# PKG900000001527.net
KiCad netlist of a schematic drawn in EAGLE
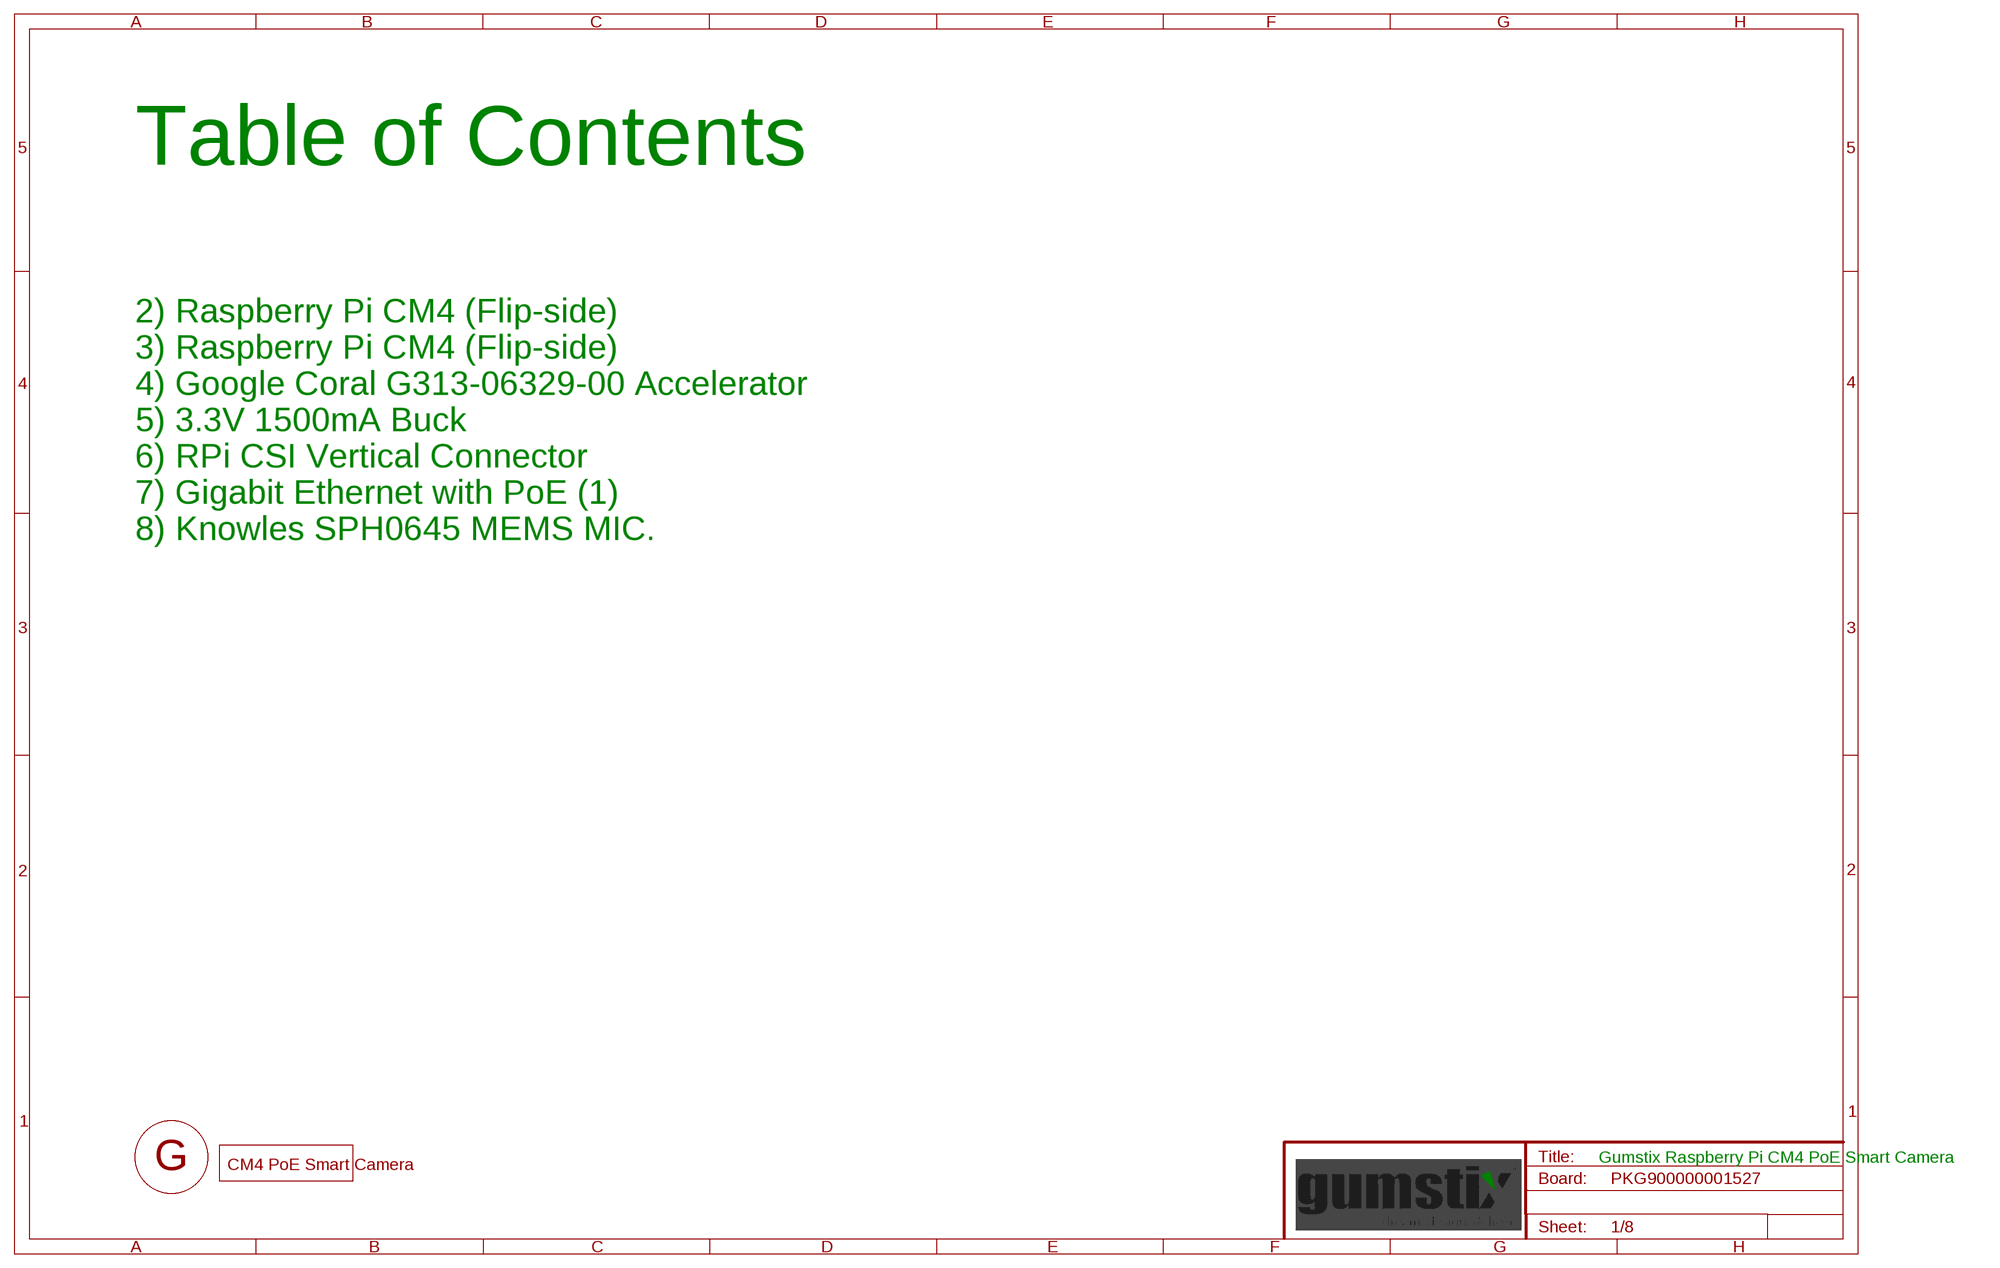
[diagram p0: schematic, sheet 1]
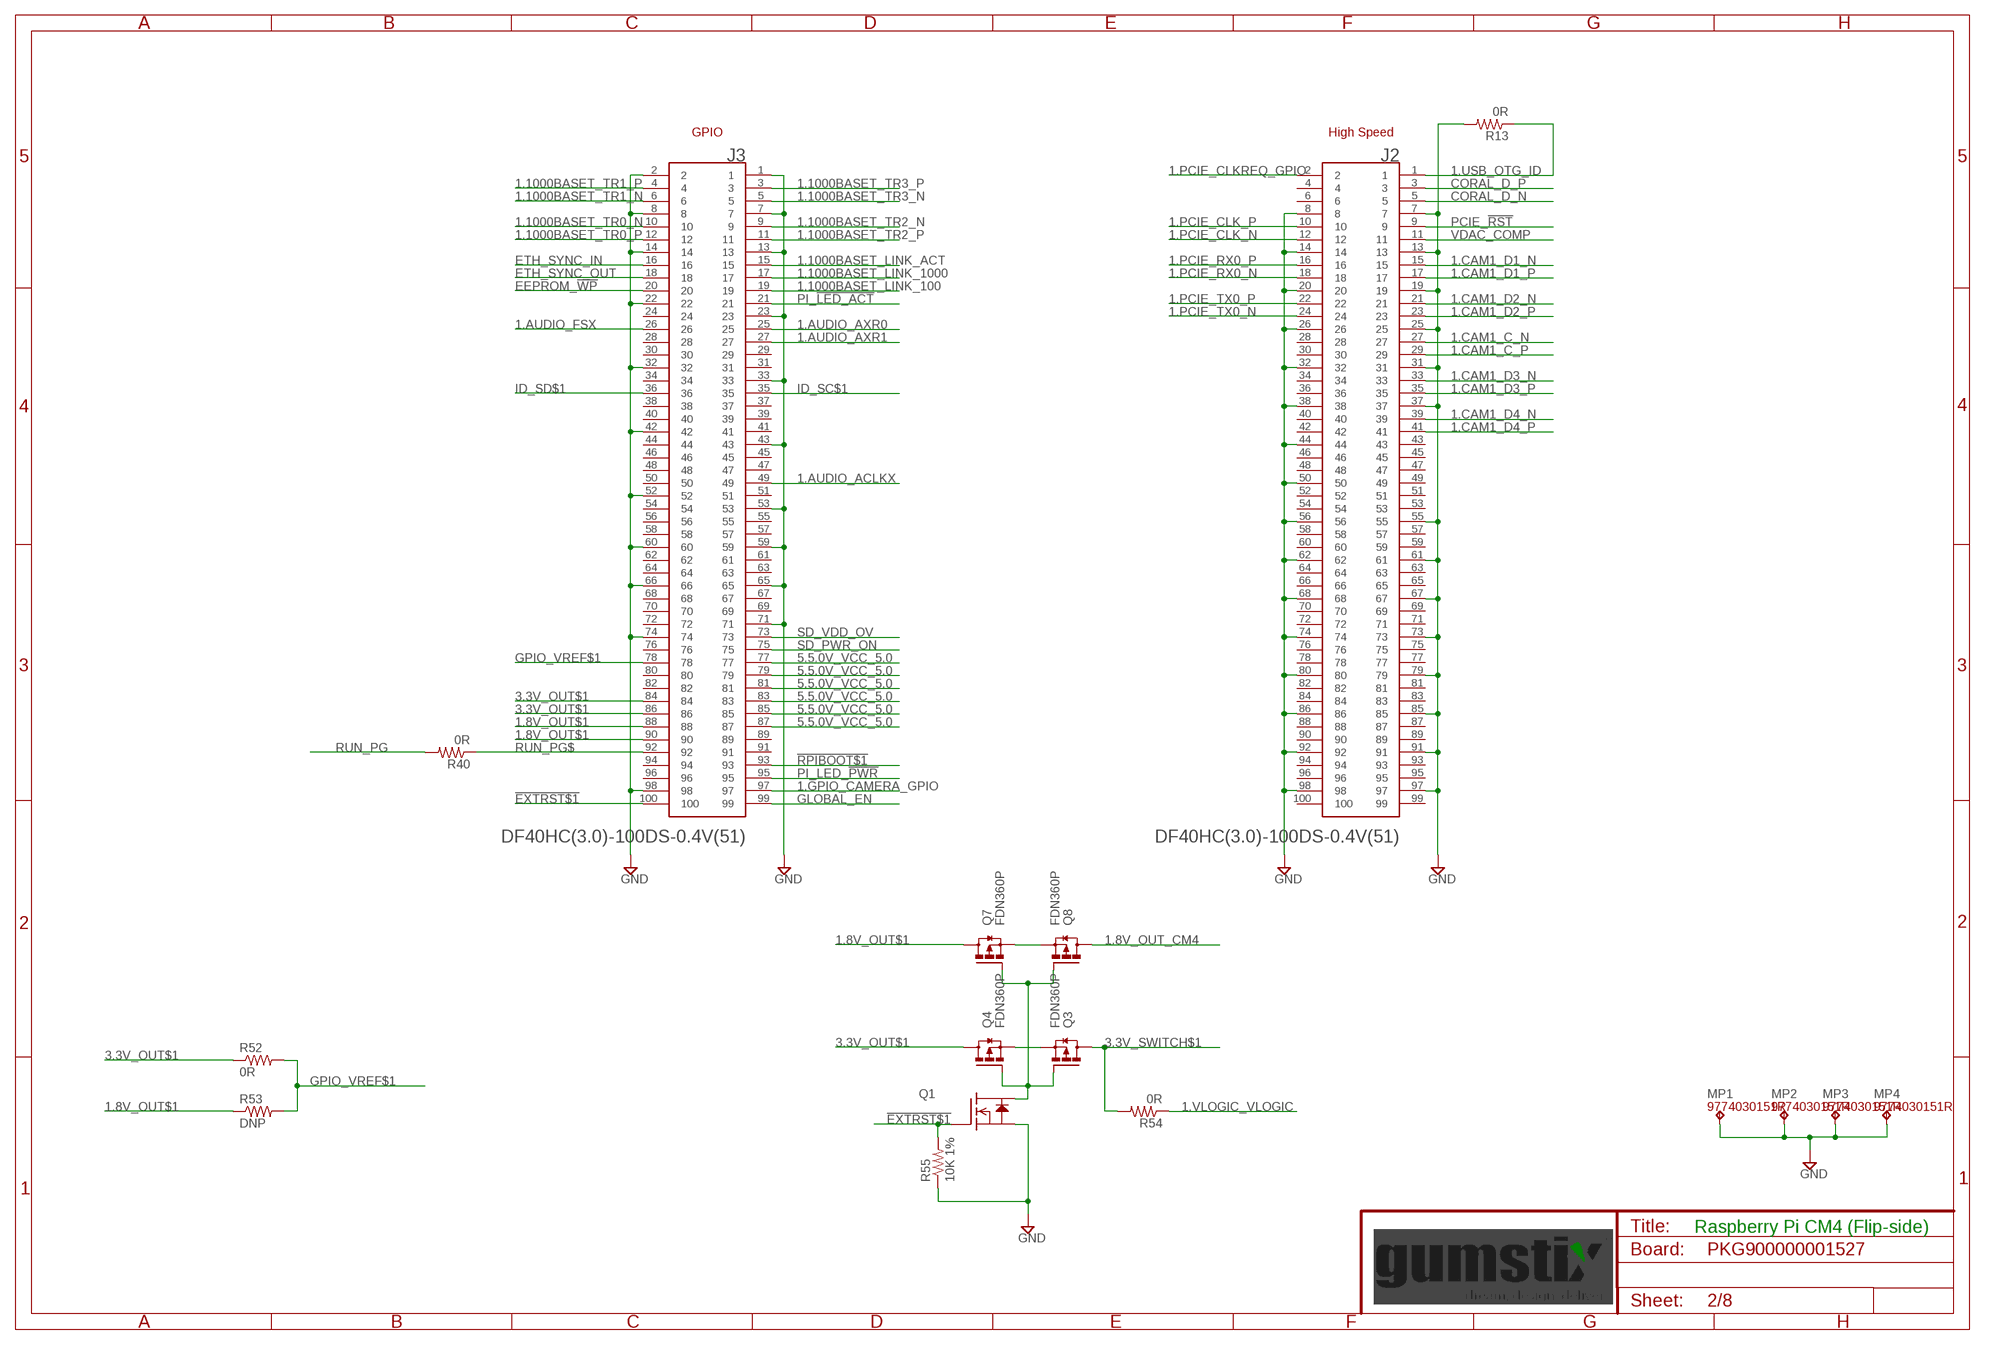
[diagram p1: schematic, sheet 2]
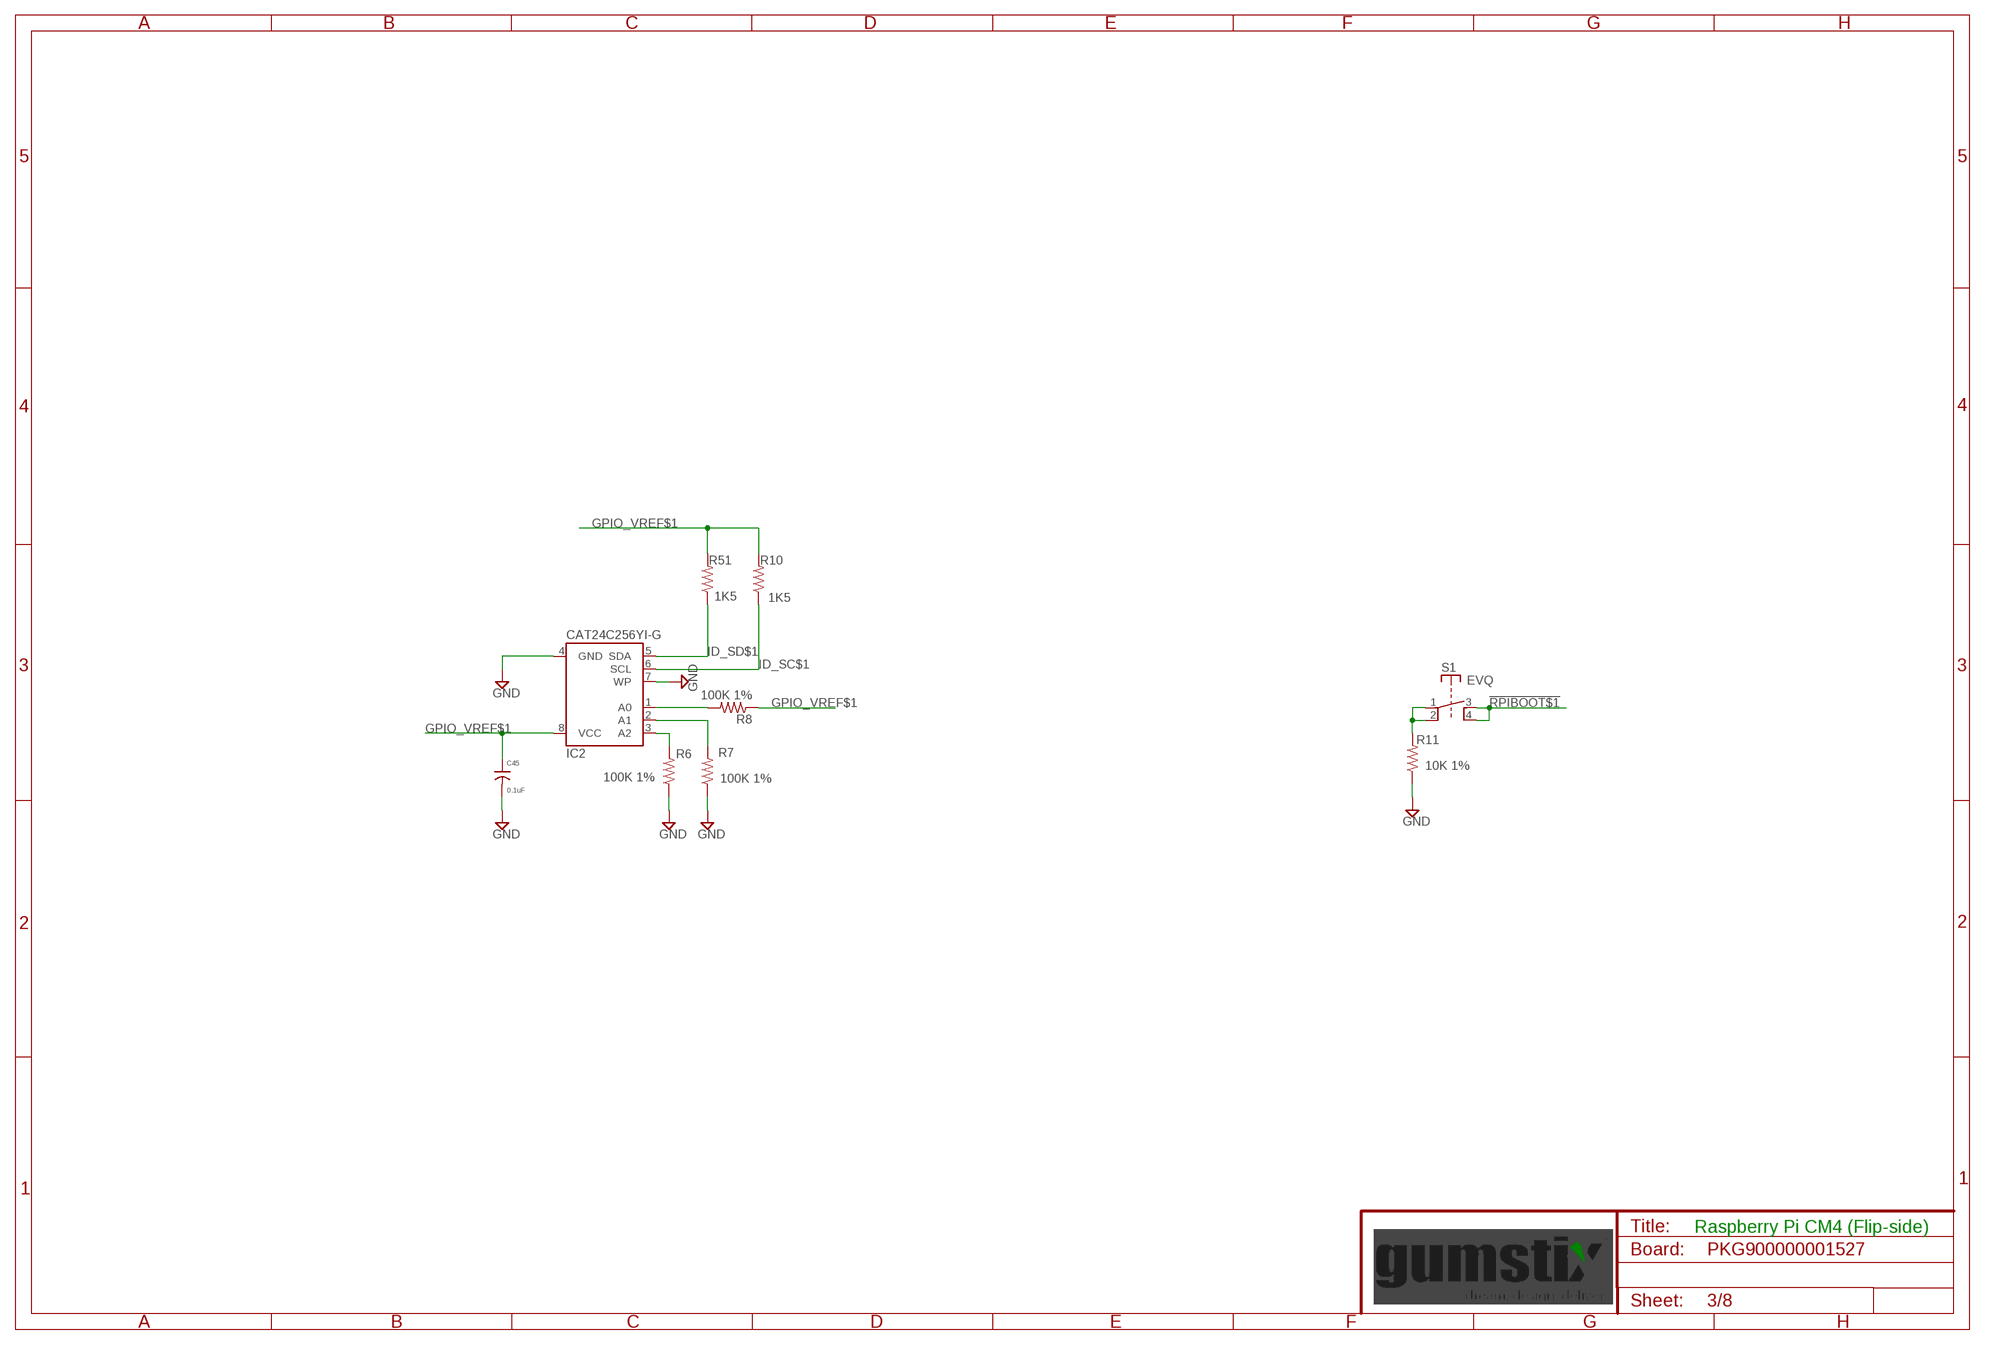
[diagram p2: schematic, sheet 3]
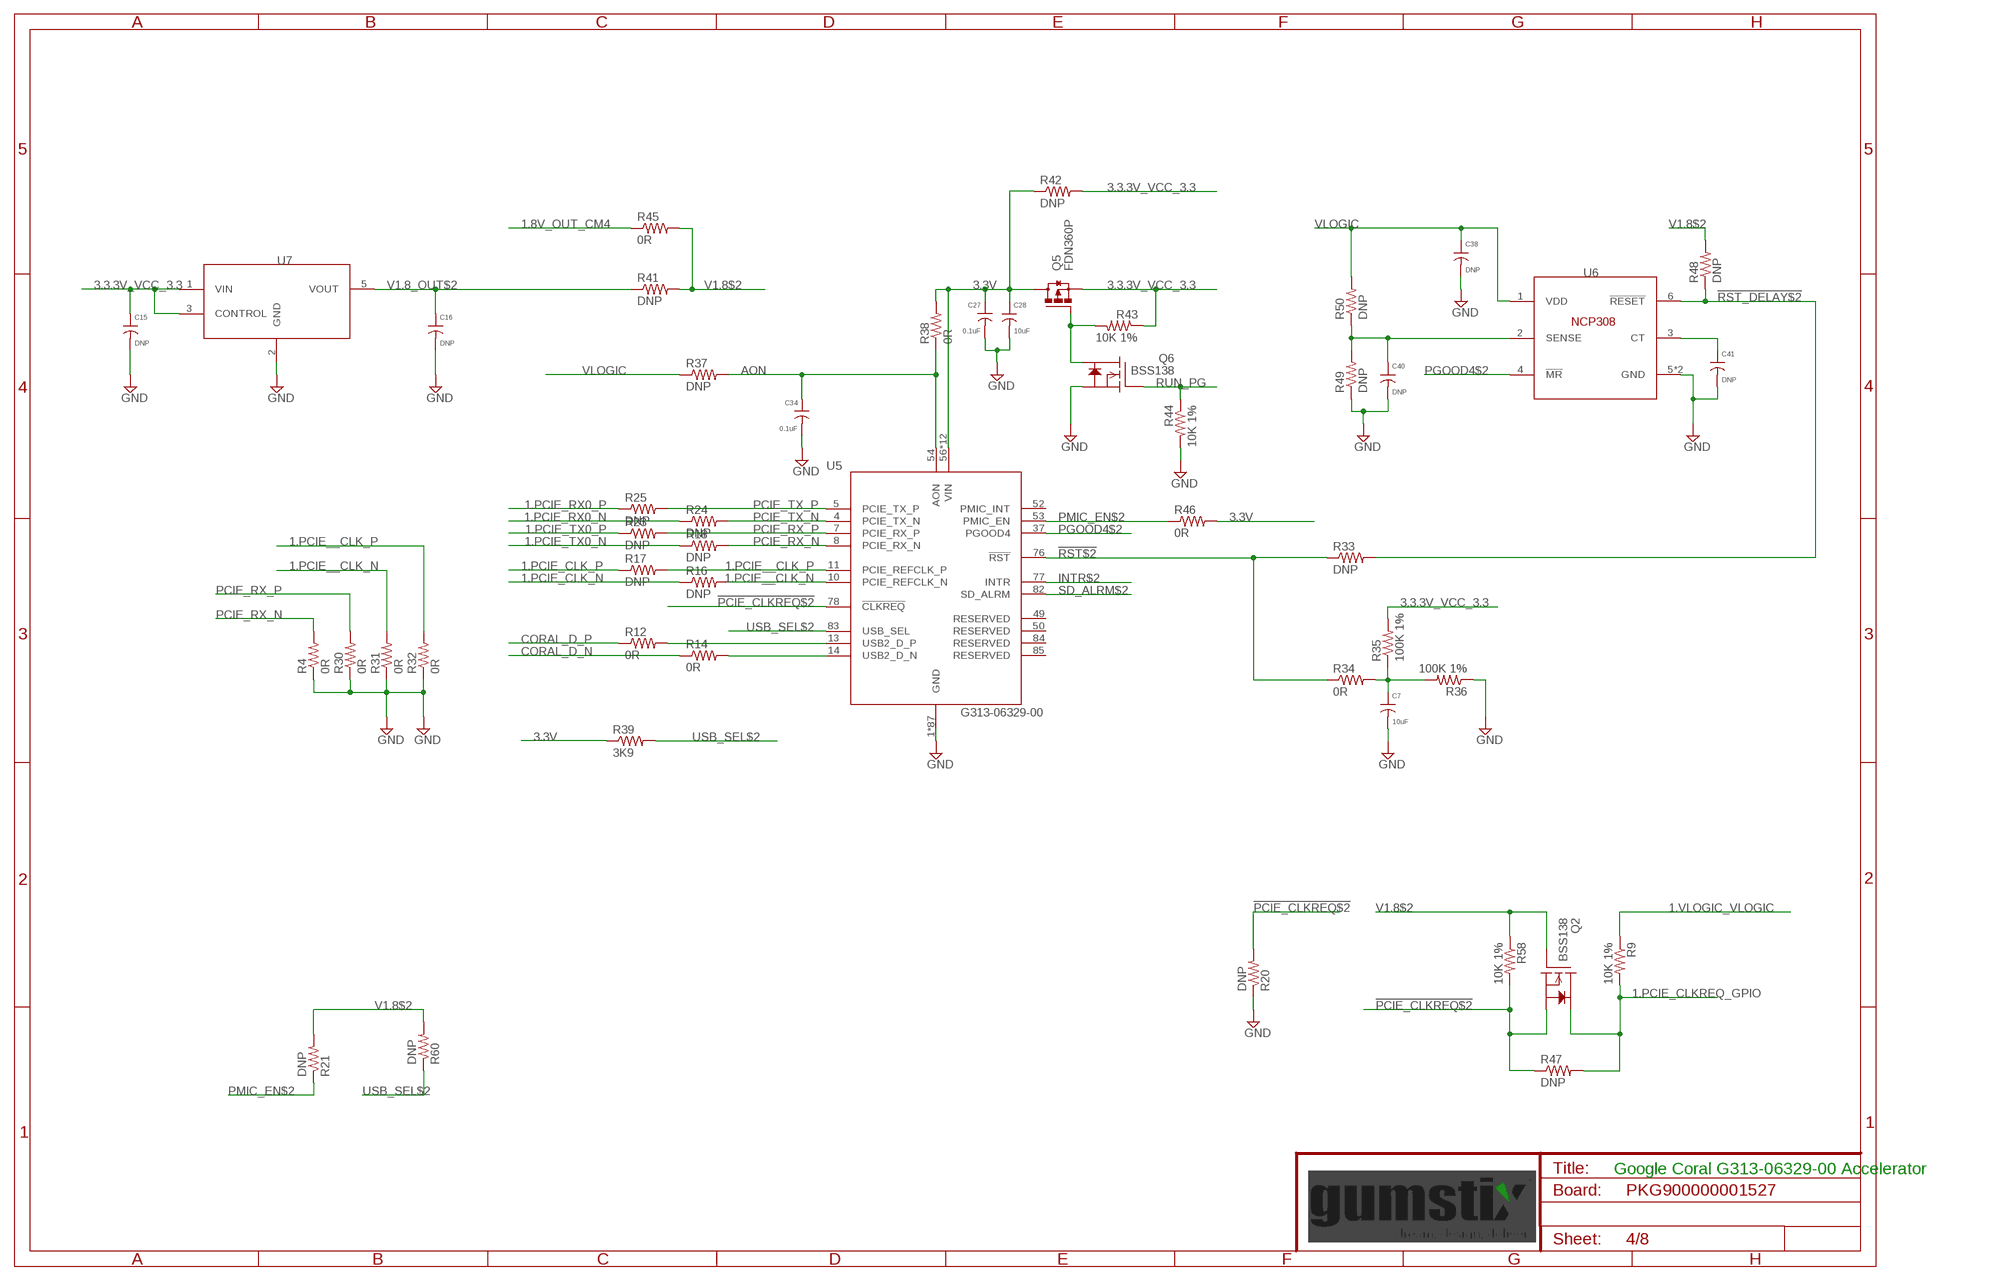
[diagram p3: schematic, sheet 4]
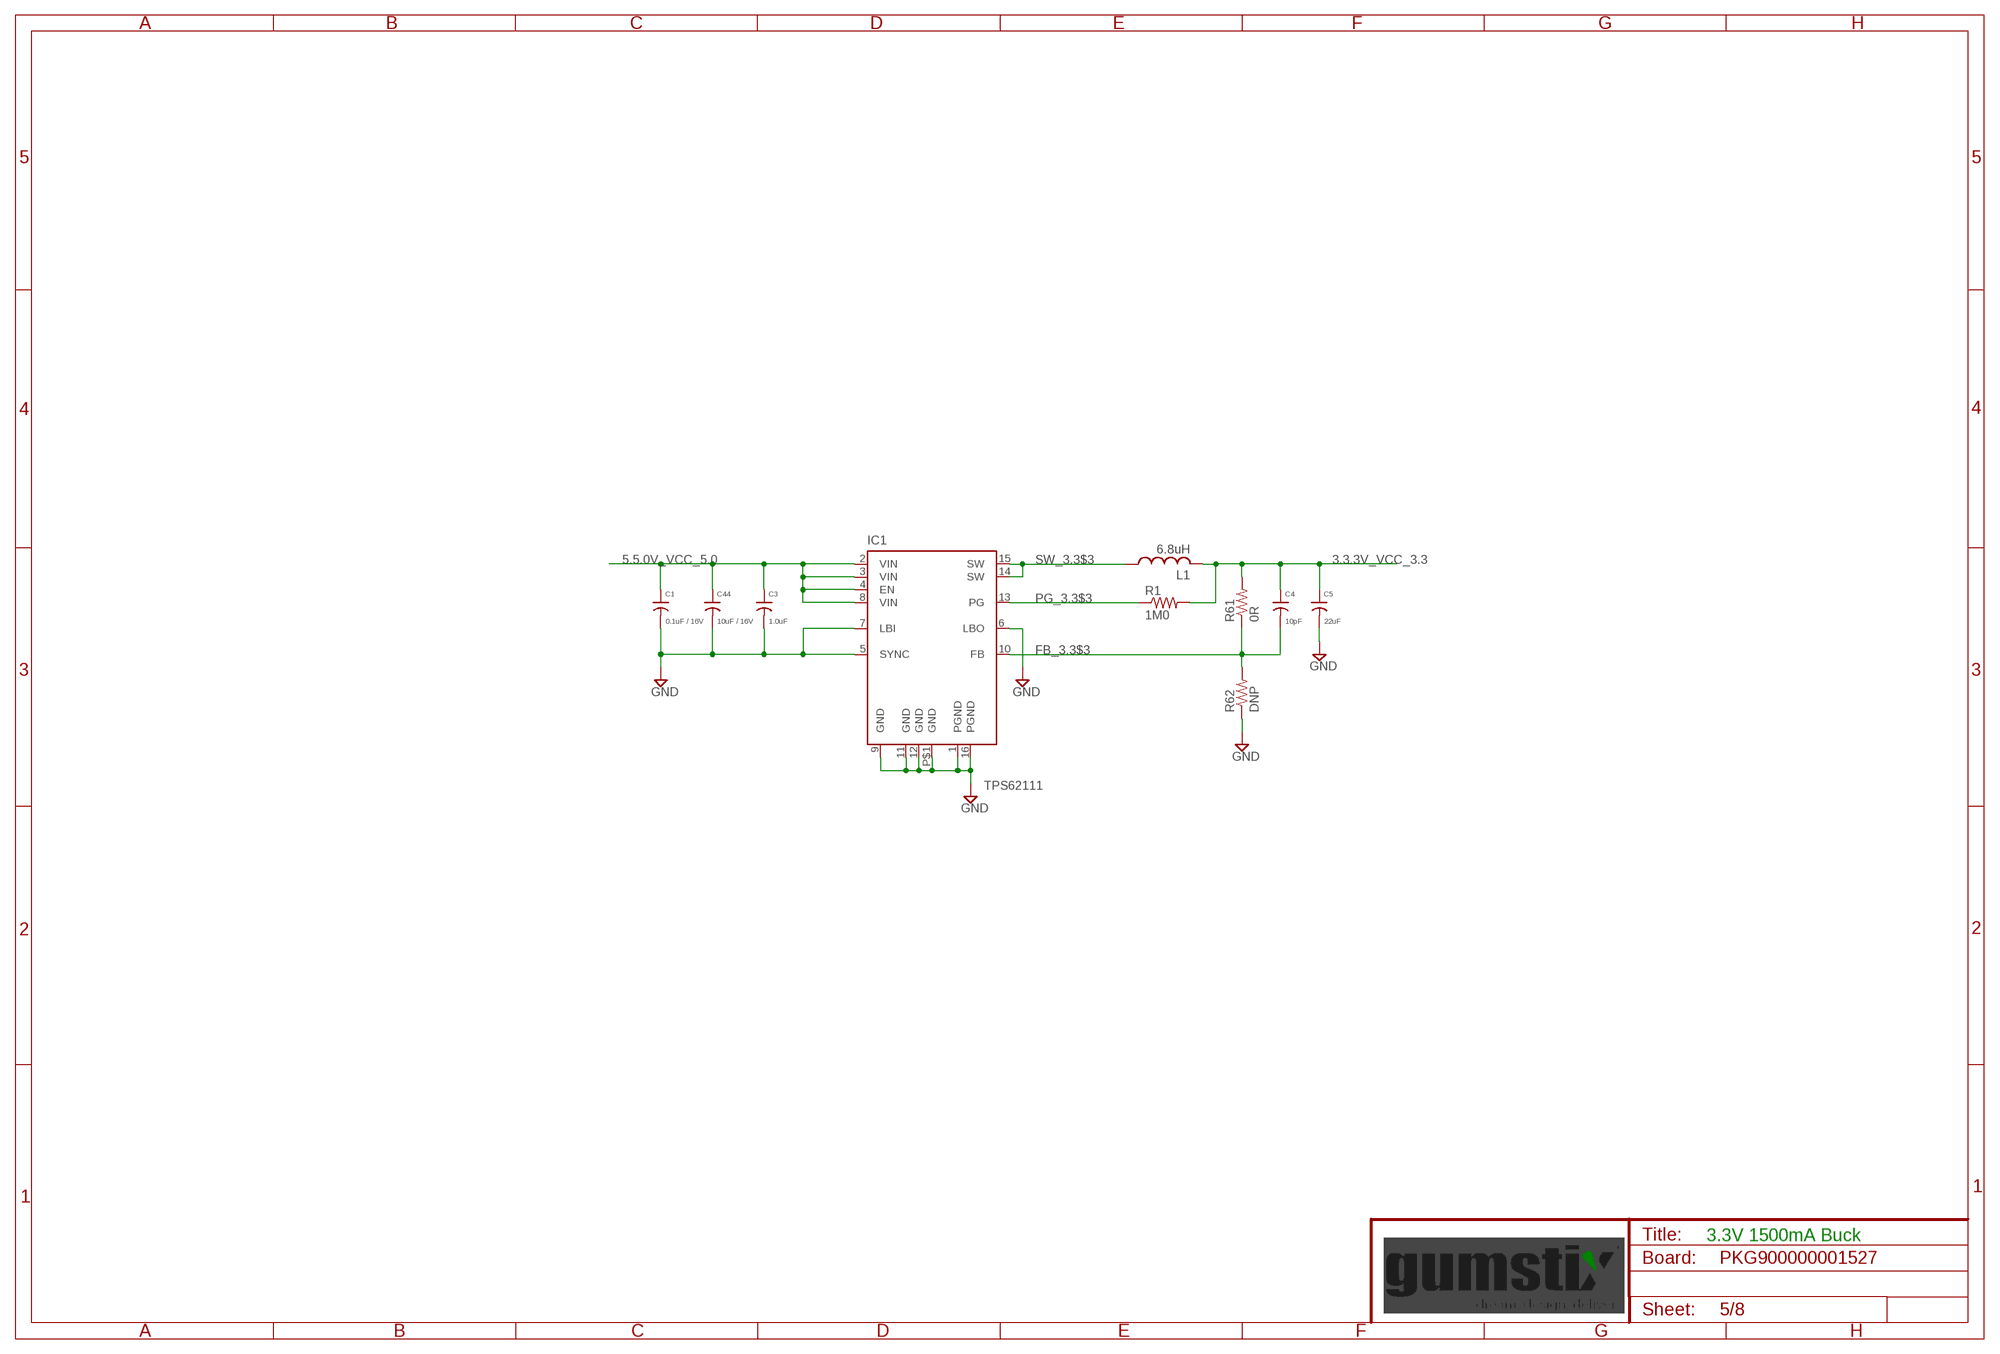
[diagram p4: schematic, sheet 5]
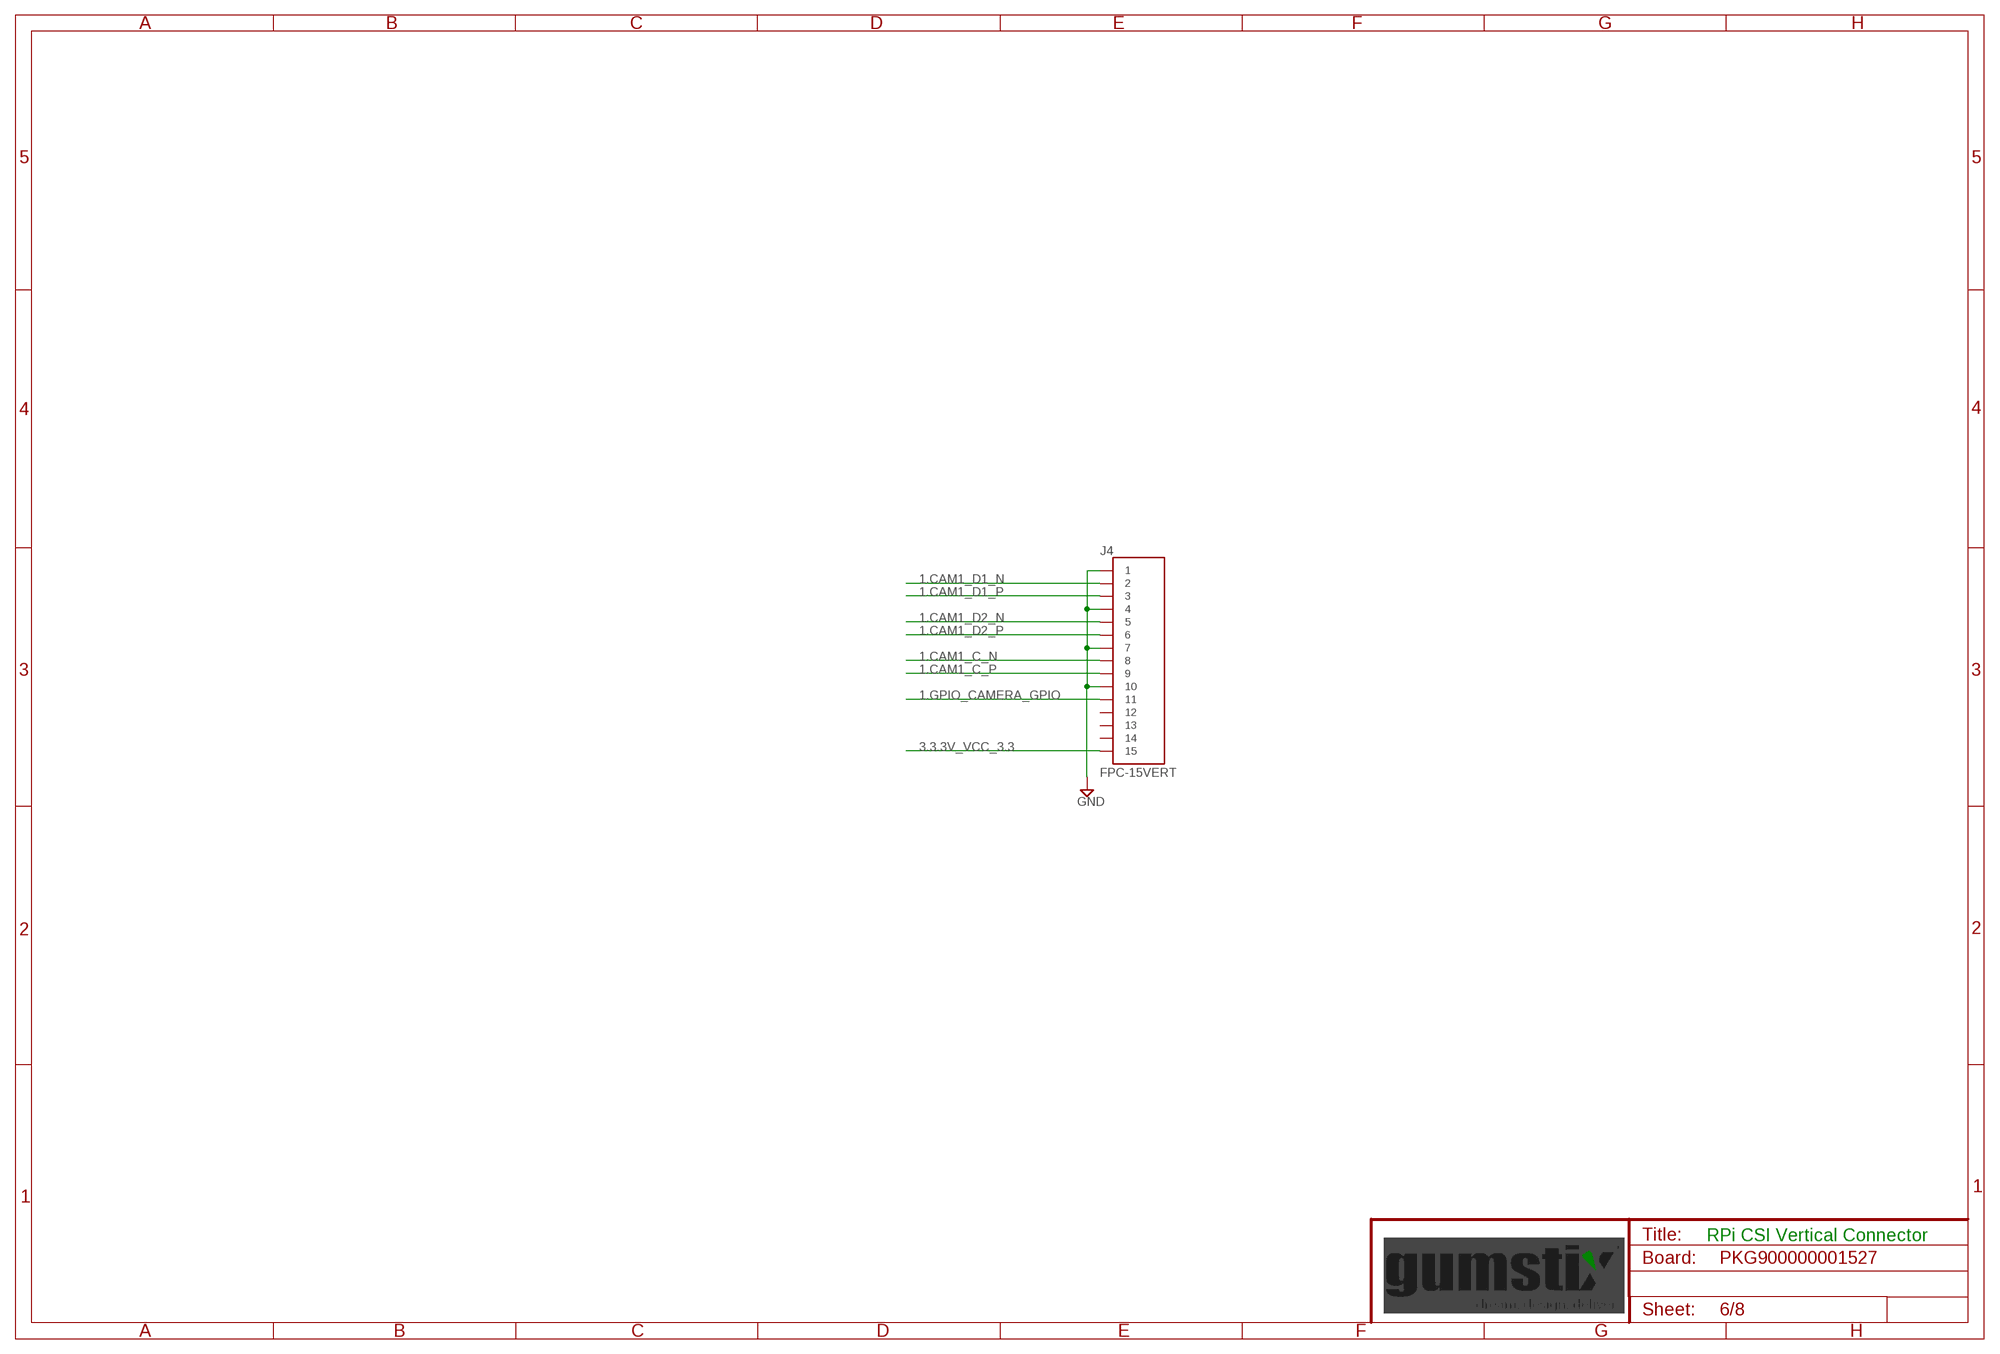
[diagram p5: schematic, sheet 6]
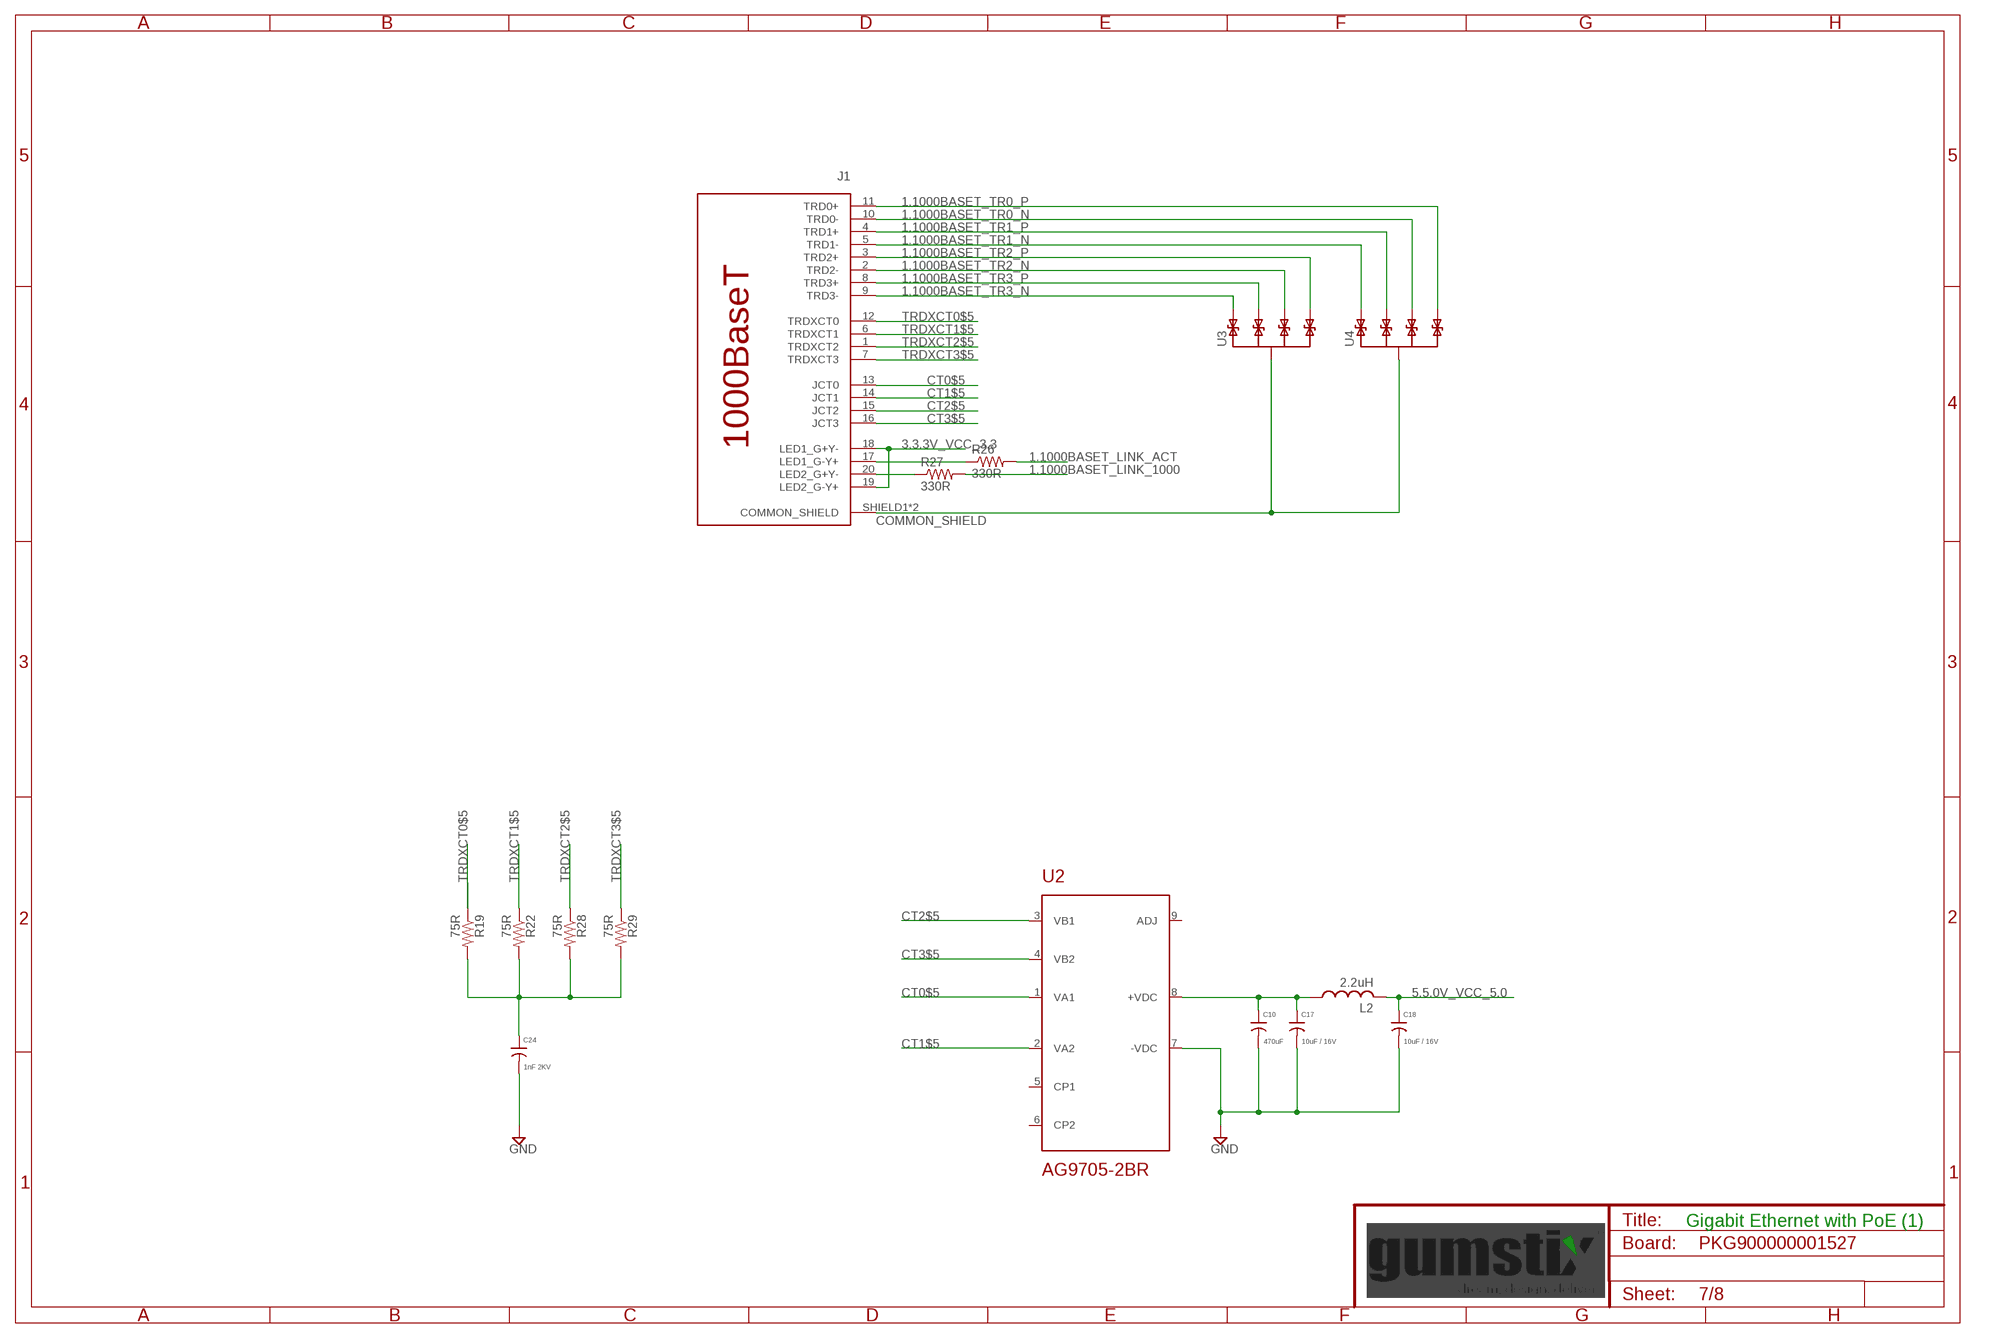
[diagram p6: schematic, sheet 7]
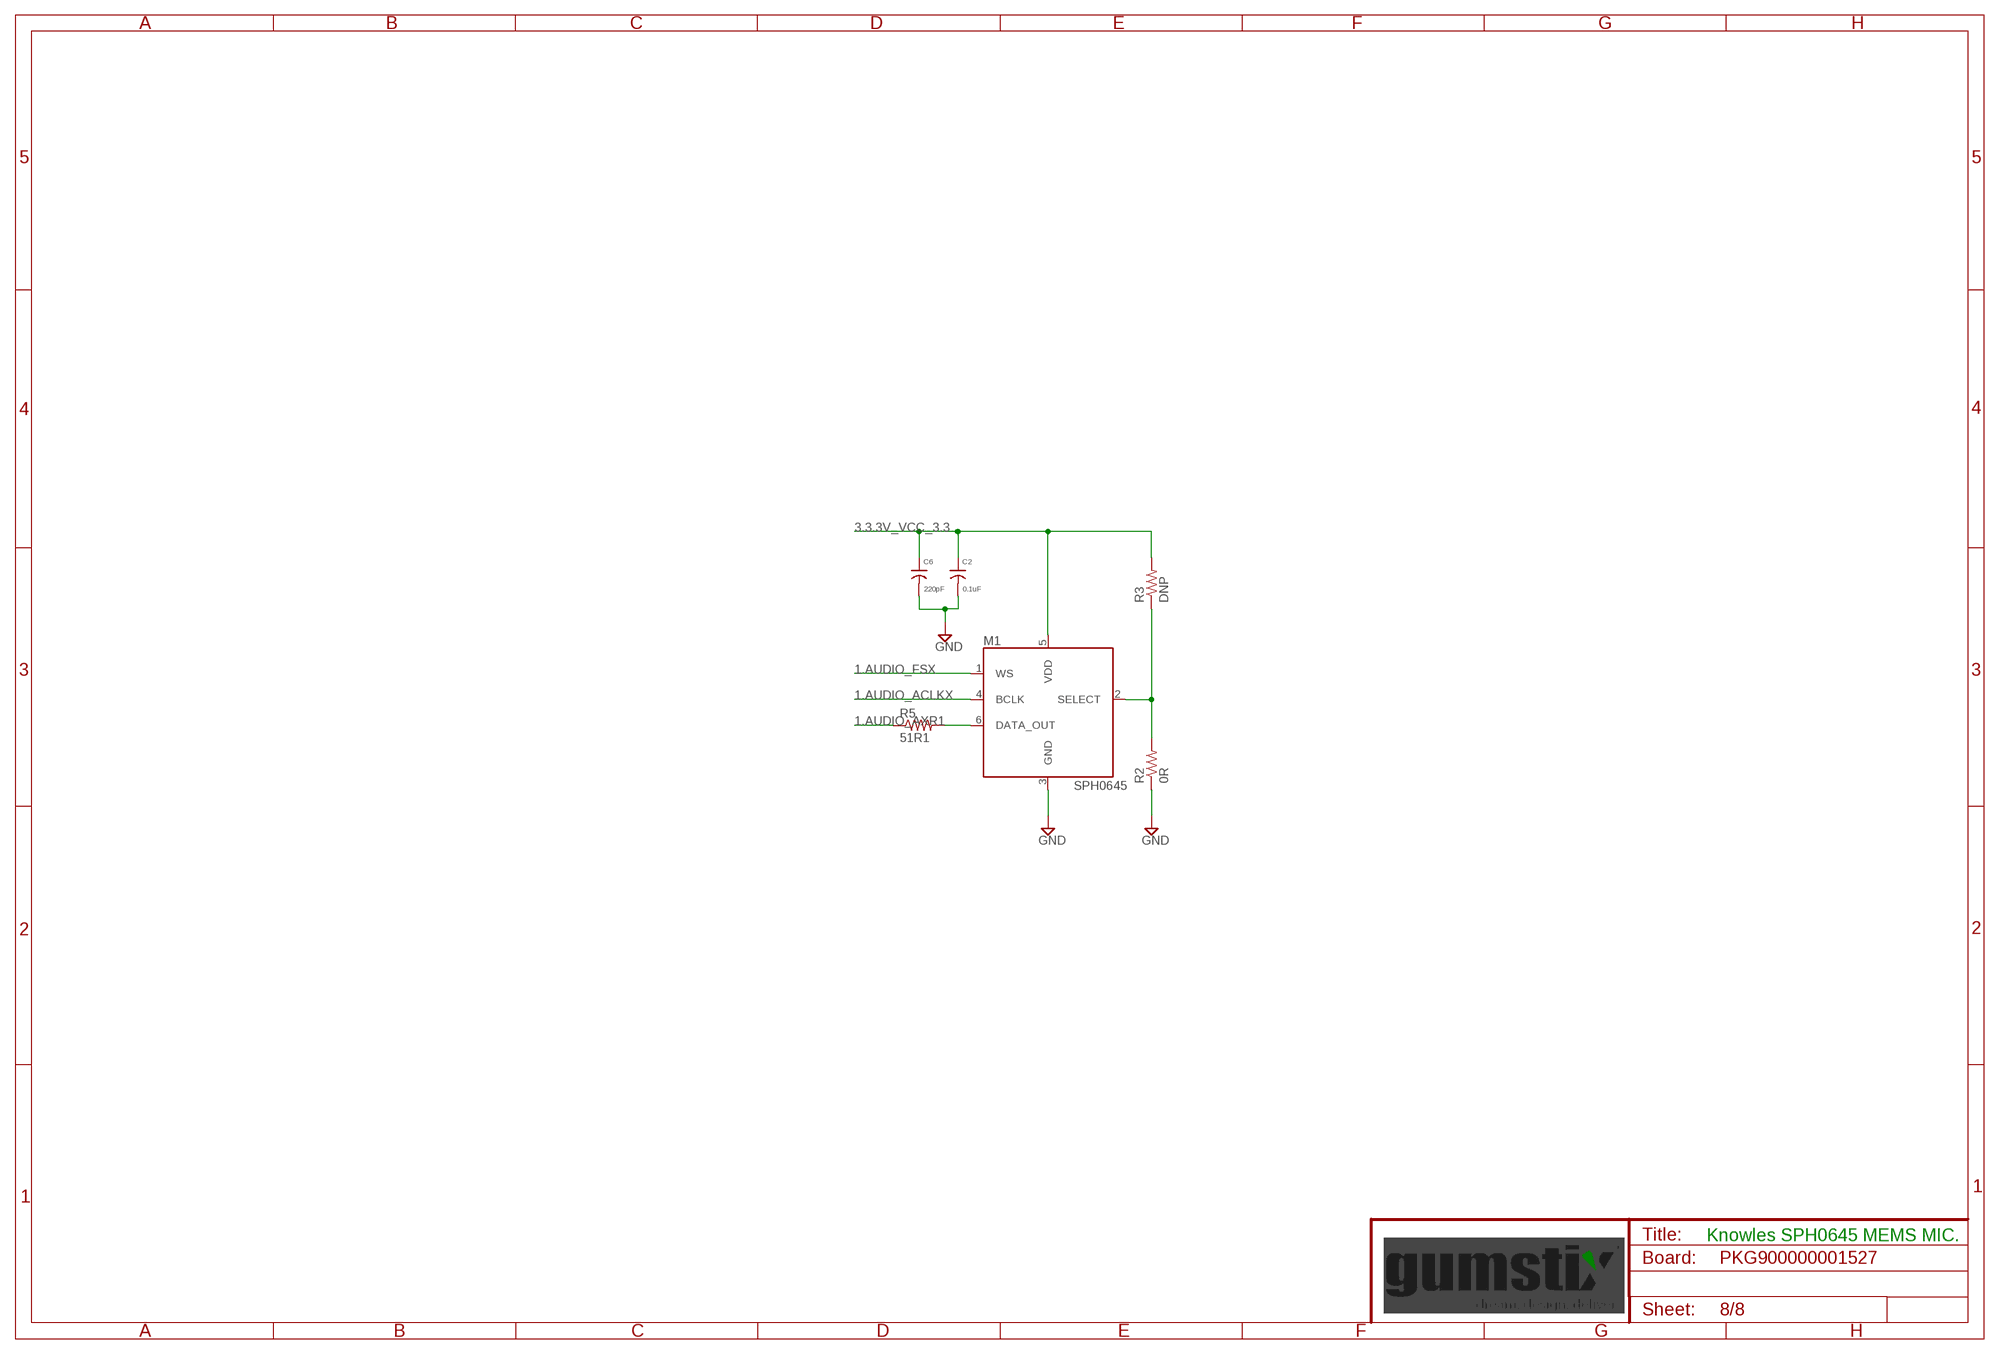
[diagram p7: schematic, sheet 8]

(export (version "E")
  (design (tool "Eeschema 10.0.6"))
  (components
    (comp (ref "C45")
      (value "0.1uF")
      (footprint "eagle-import:0201")
      (libsource (lib "eagle-import") (part "C0201"))
    )
    (comp (ref "IC2")
      (value "CAT24C256YI-G")
      (footprint "eagle-import:TSSOP8")
      (libsource (lib "eagle-import") (part "AT24CA"))
    )
    (comp (ref "R6")
      (value "100K 1%")
      (footprint "eagle-import:0201")
      (libsource (lib "eagle-import") (part "R0201"))
    )
    (comp (ref "R7")
      (value "100K 1%")
      (footprint "eagle-import:0201")
      (libsource (lib "eagle-import") (part "R0201"))
    )
    (comp (ref "R8")
      (value "100K 1%")
      (footprint "eagle-import:0201")
      (libsource (lib "eagle-import") (part "R0201"))
    )
    (comp (ref "R10")
      (value "1K5")
      (footprint "eagle-import:0201")
      (libsource (lib "eagle-import") (part "R0201"))
    )
    (comp (ref "R11")
      (value "10K 1%")
      (footprint "eagle-import:0201")
      (libsource (lib "eagle-import") (part "R0201"))
    )
    (comp (ref "R51")
      (value "1K5")
      (footprint "eagle-import:0201")
      (libsource (lib "eagle-import") (part "R0201"))
    )
    (comp (ref "S1")
      (value "EVQ")
      (footprint "eagle-import:KMT0")
      (libsource (lib "eagle-import") (part "EVQKMT0"))
    )
    (comp (ref "J2")
      (value "DF40HC(3.0)-100DS-0.4V(51)")
      (footprint "eagle-import:HRS_DF40C-100DS-0.4V(51)")
      (fields
        (field (name "DIGI-KEY_PART_NUMBER") "H11615CT-ND")
        (field (name "MF") "Hirose")
        (field (name "MP") "DF40C-100DS-0.4V_51_")
      )
      (libsource (lib "eagle-import") (part "DF40C-100DS-0.4V(51)"))
    )
    (comp (ref "J3")
      (value "DF40HC(3.0)-100DS-0.4V(51)")
      (footprint "eagle-import:HRS_DF40C-100DS-0.4V(51)")
      (fields
        (field (name "DIGI-KEY_PART_NUMBER") "H11615CT-ND")
        (field (name "MF") "Hirose")
        (field (name "MP") "DF40C-100DS-0.4V_51_")
      )
      (libsource (lib "eagle-import") (part "DF40C-100DS-0.4V(51)"))
    )
    (comp (ref "MP1")
      (value "9774030151R")
      (footprint "eagle-import:WA-SMSI_9774___151")
      (libsource (lib "eagle-import") (part "BULLET_CONN2.5MM"))
    )
    (comp (ref "MP2")
      (value "9774030151R")
      (footprint "eagle-import:WA-SMSI_9774___151")
      (libsource (lib "eagle-import") (part "BULLET_CONN2.5MM"))
    )
    (comp (ref "MP3")
      (value "9774030151R")
      (footprint "eagle-import:WA-SMSI_9774___151")
      (libsource (lib "eagle-import") (part "BULLET_CONN2.5MM"))
    )
    (comp (ref "MP4")
      (value "9774030151R")
      (footprint "eagle-import:WA-SMSI_9774___151")
      (libsource (lib "eagle-import") (part "BULLET_CONN2.5MM"))
    )
    (comp (ref "Q1")
      (value "BSS138")
      (footprint "eagle-import:SOT23")
      (libsource (lib "eagle-import") (part "BSS138"))
    )
    (comp (ref "Q3")
      (value "FDN360P")
      (footprint "eagle-import:SOT23")
      (libsource (lib "eagle-import") (part "MOSFET_P_ENH"))
    )
    (comp (ref "Q4")
      (value "FDN360P")
      (footprint "eagle-import:SOT23")
      (libsource (lib "eagle-import") (part "MOSFET_P_ENH"))
    )
    (comp (ref "Q7")
      (value "FDN360P")
      (footprint "eagle-import:SOT23")
      (libsource (lib "eagle-import") (part "MOSFET_P_ENH"))
    )
    (comp (ref "Q8")
      (value "FDN360P")
      (footprint "eagle-import:SOT23")
      (libsource (lib "eagle-import") (part "MOSFET_P_ENH"))
    )
    (comp (ref "R13")
      (value "0R")
      (footprint "eagle-import:0201")
      (libsource (lib "eagle-import") (part "R0201"))
    )
    (comp (ref "R40")
      (value "0R")
      (footprint "eagle-import:0201")
      (libsource (lib "eagle-import") (part "R0201"))
    )
    (comp (ref "R52")
      (value "0R")
      (footprint "eagle-import:0201")
      (libsource (lib "eagle-import") (part "R0201"))
    )
    (comp (ref "R53")
      (value "DNP")
      (footprint "eagle-import:0201")
      (libsource (lib "eagle-import") (part "R0201"))
    )
    (comp (ref "R54")
      (value "0R")
      (footprint "eagle-import:0201")
      (libsource (lib "eagle-import") (part "R0201"))
    )
    (comp (ref "R55")
      (value "10K 1%")
      (footprint "eagle-import:0201")
      (libsource (lib "eagle-import") (part "R0201"))
    )
    (comp (ref "C1")
      (value "0.1uF / 16V")
      (footprint "eagle-import:0402")
      (libsource (lib "eagle-import") (part "C0402"))
    )
    (comp (ref "C3")
      (value "1.0uF")
      (footprint "eagle-import:0402")
      (libsource (lib "eagle-import") (part "C0402"))
    )
    (comp (ref "C4")
      (value "10pF")
      (footprint "eagle-import:0201")
      (libsource (lib "eagle-import") (part "C0201"))
    )
    (comp (ref "C5")
      (value "22uF")
      (footprint "eagle-import:0805")
      (libsource (lib "eagle-import") (part "C0805"))
    )
    (comp (ref "C44")
      (value "10uF / 16V")
      (footprint "eagle-import:0805")
      (libsource (lib "eagle-import") (part "C0805"))
    )
    (comp (ref "IC1")
      (value "TPS62111")
      (footprint "eagle-import:PQFP16")
      (libsource (lib "eagle-import") (part "TPS62111"))
    )
    (comp (ref "L1")
      (value "6.8uH")
      (footprint "eagle-import:1515")
      (libsource (lib "eagle-import") (part "L1515"))
    )
    (comp (ref "R1")
      (value "1M0")
      (footprint "eagle-import:0201")
      (libsource (lib "eagle-import") (part "R0201"))
    )
    (comp (ref "R61")
      (value "0R")
      (footprint "eagle-import:0402")
      (libsource (lib "eagle-import") (part "R0402"))
    )
    (comp (ref "R62")
      (value "DNP")
      (footprint "eagle-import:0402")
      (libsource (lib "eagle-import") (part "R0402"))
    )
    (comp (ref "J4")
      (value "FPC-15VERT")
      (footprint "eagle-import:1-1734248-5")
      (libsource (lib "eagle-import") (part "FPC-15VERT"))
    )
    (comp (ref "C7")
      (value "10uF")
      (footprint "eagle-import:0603")
      (libsource (lib "eagle-import") (part "C0603"))
    )
    (comp (ref "C15")
      (value "DNP")
      (footprint "eagle-import:0201")
      (libsource (lib "eagle-import") (part "C0201"))
    )
    (comp (ref "C16")
      (value "DNP")
      (footprint "eagle-import:0402")
      (libsource (lib "eagle-import") (part "C0402"))
    )
    (comp (ref "C27")
      (value "0.1uF")
      (footprint "eagle-import:0201")
      (libsource (lib "eagle-import") (part "C0201"))
    )
    (comp (ref "C28")
      (value "10uF")
      (footprint "eagle-import:0603")
      (libsource (lib "eagle-import") (part "C0603"))
    )
    (comp (ref "C34")
      (value "0.1uF")
      (footprint "eagle-import:0201")
      (libsource (lib "eagle-import") (part "C0201"))
    )
    (comp (ref "C38")
      (value "DNP")
      (footprint "eagle-import:0201")
      (libsource (lib "eagle-import") (part "C0201"))
    )
    (comp (ref "C40")
      (value "DNP")
      (footprint "eagle-import:0201")
      (libsource (lib "eagle-import") (part "C0201"))
    )
    (comp (ref "C41")
      (value "DNP")
      (footprint "eagle-import:0201")
      (libsource (lib "eagle-import") (part "C0201"))
    )
    (comp (ref "Q2")
      (value "BSS138")
      (footprint "eagle-import:SOT23")
      (libsource (lib "eagle-import") (part "BSS138"))
    )
    (comp (ref "Q5")
      (value "FDN360P")
      (footprint "eagle-import:SOT23")
      (libsource (lib "eagle-import") (part "MOSFET_P_ENH"))
    )
    (comp (ref "Q6")
      (value "BSS138")
      (footprint "eagle-import:SOT23")
      (libsource (lib "eagle-import") (part "BSS138"))
    )
    (comp (ref "R4")
      (value "0R")
      (footprint "eagle-import:0201")
      (libsource (lib "eagle-import") (part "R0201"))
    )
    (comp (ref "R9")
      (value "10K 1%")
      (footprint "eagle-import:0201")
      (libsource (lib "eagle-import") (part "R0201"))
    )
    (comp (ref "R12")
      (value "0R")
      (footprint "eagle-import:0201")
      (libsource (lib "eagle-import") (part "R0201"))
    )
    (comp (ref "R14")
      (value "0R")
      (footprint "eagle-import:0201")
      (libsource (lib "eagle-import") (part "R0201"))
    )
    (comp (ref "R16")
      (value "DNP")
      (footprint "eagle-import:0201")
      (libsource (lib "eagle-import") (part "R0201"))
    )
    (comp (ref "R17")
      (value "DNP")
      (footprint "eagle-import:0201")
      (libsource (lib "eagle-import") (part "R0201"))
    )
    (comp (ref "R18")
      (value "DNP")
      (footprint "eagle-import:0201")
      (libsource (lib "eagle-import") (part "R0201"))
    )
    (comp (ref "R20")
      (value "DNP")
      (footprint "eagle-import:0201")
      (libsource (lib "eagle-import") (part "R0201"))
    )
    (comp (ref "R21")
      (value "DNP")
      (footprint "eagle-import:0201")
      (libsource (lib "eagle-import") (part "R0201"))
    )
    (comp (ref "R23")
      (value "DNP")
      (footprint "eagle-import:0201")
      (libsource (lib "eagle-import") (part "R0201"))
    )
    (comp (ref "R24")
      (value "DNP")
      (footprint "eagle-import:0201")
      (libsource (lib "eagle-import") (part "R0201"))
    )
    (comp (ref "R25")
      (value "DNP")
      (footprint "eagle-import:0201")
      (libsource (lib "eagle-import") (part "R0201"))
    )
    (comp (ref "R30")
      (value "0R")
      (footprint "eagle-import:0201")
      (libsource (lib "eagle-import") (part "R0201"))
    )
    (comp (ref "R31")
      (value "0R")
      (footprint "eagle-import:0201")
      (libsource (lib "eagle-import") (part "R0201"))
    )
    (comp (ref "R32")
      (value "0R")
      (footprint "eagle-import:0201")
      (libsource (lib "eagle-import") (part "R0201"))
    )
    (comp (ref "R33")
      (value "DNP")
      (footprint "eagle-import:0201")
      (libsource (lib "eagle-import") (part "R0201"))
    )
    (comp (ref "R34")
      (value "0R")
      (footprint "eagle-import:0201")
      (libsource (lib "eagle-import") (part "R0201"))
    )
    (comp (ref "R35")
      (value "100K 1%")
      (footprint "eagle-import:0201")
      (libsource (lib "eagle-import") (part "R0201"))
    )
    (comp (ref "R36")
      (value "100K 1%")
      (footprint "eagle-import:0201")
      (libsource (lib "eagle-import") (part "R0201"))
    )
    (comp (ref "R37")
      (value "DNP")
      (footprint "eagle-import:0201")
      (libsource (lib "eagle-import") (part "R0201"))
    )
    (comp (ref "R38")
      (value "0R")
      (footprint "eagle-import:0201")
      (libsource (lib "eagle-import") (part "R0201"))
    )
    (comp (ref "R39")
      (value "3K9")
      (footprint "eagle-import:0201")
      (libsource (lib "eagle-import") (part "R0201"))
    )
    (comp (ref "R41")
      (value "DNP")
      (footprint "eagle-import:0603")
      (libsource (lib "eagle-import") (part "R0603"))
    )
    (comp (ref "R42")
      (value "DNP")
      (footprint "eagle-import:0805")
      (libsource (lib "eagle-import") (part "R0805"))
    )
    (comp (ref "R43")
      (value "10K 1%")
      (footprint "eagle-import:0201")
      (libsource (lib "eagle-import") (part "R0201"))
    )
    (comp (ref "R44")
      (value "10K 1%")
      (footprint "eagle-import:0201")
      (libsource (lib "eagle-import") (part "R0201"))
    )
    (comp (ref "R45")
      (value "0R")
      (footprint "eagle-import:0603")
      (libsource (lib "eagle-import") (part "R0603"))
    )
    (comp (ref "R46")
      (value "0R")
      (footprint "eagle-import:0201")
      (libsource (lib "eagle-import") (part "R0201"))
    )
    (comp (ref "R47")
      (value "DNP")
      (footprint "eagle-import:0201")
      (libsource (lib "eagle-import") (part "R0201"))
    )
    (comp (ref "R48")
      (value "DNP")
      (footprint "eagle-import:0201")
      (libsource (lib "eagle-import") (part "R0201"))
    )
    (comp (ref "R49")
      (value "DNP")
      (footprint "eagle-import:0201")
      (libsource (lib "eagle-import") (part "R0201"))
    )
    (comp (ref "R50")
      (value "DNP")
      (footprint "eagle-import:0201")
      (libsource (lib "eagle-import") (part "R0201"))
    )
    (comp (ref "R58")
      (value "10K 1%")
      (footprint "eagle-import:0201")
      (libsource (lib "eagle-import") (part "R0201"))
    )
    (comp (ref "R60")
      (value "DNP")
      (footprint "eagle-import:0201")
      (libsource (lib "eagle-import") (part "R0201"))
    )
    (comp (ref "U5")
      (value "G313-06329-00")
      (footprint "eagle-import:G313-06329-00")
      (libsource (lib "eagle-import") (part "G313-06329-00"))
    )
    (comp (ref "U6")
      (value "DNP")
      (footprint "eagle-import:WDFN6")
      (libsource (lib "eagle-import") (part "NCP308"))
    )
    (comp (ref "U7")
      (value "DNP")
      (footprint "eagle-import:SOT-23-5")
      (libsource (lib "eagle-import") (part "TCR2EF18"))
    )
    (comp (ref "C10")
      (value "470uF")
      (footprint "eagle-import:PANASONIC_F")
      (libsource (lib "eagle-import") (part "CPANASONIC_F"))
    )
    (comp (ref "C17")
      (value "10uF / 16V")
      (footprint "eagle-import:0805")
      (libsource (lib "eagle-import") (part "C0805"))
    )
    (comp (ref "C18")
      (value "10uF / 16V")
      (footprint "eagle-import:0805")
      (libsource (lib "eagle-import") (part "C0805"))
    )
    (comp (ref "C24")
      (value "1nF 2KV")
      (footprint "eagle-import:1206")
      (libsource (lib "eagle-import") (part "C1206"))
    )
    (comp (ref "J1")
      (value "1000BASET_POE")
      (footprint "eagle-import:7499511440")
      (libsource (lib "eagle-import") (part "1000BASET_POE"))
    )
    (comp (ref "L2")
      (value "2.2uH")
      (footprint "eagle-import:1515")
      (libsource (lib "eagle-import") (part "L1515"))
    )
    (comp (ref "R19")
      (value "75R")
      (footprint "eagle-import:0402")
      (libsource (lib "eagle-import") (part "R0402"))
    )
    (comp (ref "R22")
      (value "75R")
      (footprint "eagle-import:0402")
      (libsource (lib "eagle-import") (part "R0402"))
    )
    (comp (ref "R26")
      (value "330R")
      (footprint "eagle-import:0402")
      (libsource (lib "eagle-import") (part "R0402"))
    )
    (comp (ref "R27")
      (value "330R")
      (footprint "eagle-import:0402")
      (libsource (lib "eagle-import") (part "R0402"))
    )
    (comp (ref "R28")
      (value "75R")
      (footprint "eagle-import:0402")
      (libsource (lib "eagle-import") (part "R0402"))
    )
    (comp (ref "R29")
      (value "75R")
      (footprint "eagle-import:0402")
      (libsource (lib "eagle-import") (part "R0402"))
    )
    (comp (ref "U2")
      (value "AG9705-2BR")
      (footprint "eagle-import:AG9700")
      (libsource (lib "eagle-import") (part "AG9700"))
    )
    (comp (ref "U3")
      (value "TPD4E02B0410-USON")
      (footprint "eagle-import:UFDFN-10")
      (libsource (lib "eagle-import") (part "TPD4E02B0410-USON"))
    )
    (comp (ref "U4")
      (value "TPD4E02B0410-USON")
      (footprint "eagle-import:UFDFN-10")
      (libsource (lib "eagle-import") (part "TPD4E02B0410-USON"))
    )
    (comp (ref "C2")
      (value "0.1uF")
      (footprint "eagle-import:0201")
      (libsource (lib "eagle-import") (part "C0201"))
    )
    (comp (ref "C6")
      (value "220pF")
      (footprint "eagle-import:0201")
      (libsource (lib "eagle-import") (part "C0201"))
    )
    (comp (ref "M1")
      (value "SPH0645")
      (footprint "eagle-import:SPH0645")
      (fields
        (field (name "DIGI-KEY_PART_NUMBER") "423-1405-1-ND")
        (field (name "MF") "Knowles")
        (field (name "MP") "SPH0645LM4H-B")
      )
      (libsource (lib "eagle-import") (part "SPH0645LM4H-B"))
    )
    (comp (ref "R2")
      (value "0R")
      (footprint "eagle-import:0201")
      (libsource (lib "eagle-import") (part "R0201"))
    )
    (comp (ref "R3")
      (value "DNP")
      (footprint "eagle-import:0201")
      (libsource (lib "eagle-import") (part "R0201"))
    )
    (comp (ref "R5")
      (value "51R1")
      (footprint "eagle-import:0402")
      (libsource (lib "eagle-import") (part "R0402"))
    )
    (comp (ref "FD1")
      (value "DNP")
      (footprint "eagle-import:FIDUCIAL")
      (libsource (lib "eagle-import") (part "FIDUCIAL"))
    )
    (comp (ref "FD2")
      (value "DNP")
      (footprint "eagle-import:FIDUCIAL")
      (libsource (lib "eagle-import") (part "FIDUCIAL"))
    )
    (comp (ref "FD3")
      (value "DNP")
      (footprint "eagle-import:FIDUCIAL")
      (libsource (lib "eagle-import") (part "FIDUCIAL"))
    )
    (comp (ref "FD4")
      (value "DNP")
      (footprint "eagle-import:FIDUCIAL")
      (libsource (lib "eagle-import") (part "FIDUCIAL"))
    )
    (comp (ref "FD5")
      (value "DNP")
      (footprint "eagle-import:FIDUCIAL")
      (libsource (lib "eagle-import") (part "FIDUCIAL"))
    )
    (comp (ref "FD6")
      (value "DNP")
      (footprint "eagle-import:FIDUCIAL")
      (libsource (lib "eagle-import") (part "FIDUCIAL"))
    )
    (comp (ref "U$2")
      (value "DNP")
      (footprint "eagle-import:GEPPETTO_LABEL")
      (fields
        (field (name "BOARD") "PCB900000001527v1")
        (field (name "TITLE") "CM4 PoE Smart Camera")
        (field (name "YEAR") "2020")
      )
      (libsource (lib "eagle-import") (part "GEPPETTO_LABEL{dblquote}"))
    )
    (comp (ref "U$3")
      (value "DNP")
      (footprint "eagle-import:GEPPETTO_LOGO_SILK10")
      (libsource (lib "eagle-import") (part "GEPPETTO_LOGO10X10"))
    )
  )
  (nets
    (net (code "1") (name "1.8V_OUT$1") (class "Default")
      (node (ref "J3") (pin "88") (pinfunction "88_88") (pintype "passive"))
      (node (ref "J3") (pin "90") (pinfunction "90_90") (pintype "passive"))
      (node (ref "Q7") (pin "3") (pinfunction "D_3") (pintype "passive"))
      (node (ref "R53") (pin "1") (pinfunction "1_1") (pintype "passive"))
    )
    (net (code "2") (name "1.8V_OUT_CM4") (class "Default")
      (node (ref "Q8") (pin "3") (pinfunction "D_3") (pintype "passive"))
      (node (ref "R45") (pin "1") (pinfunction "1_1") (pintype "passive"))
    )
    (net (code "3") (name "1.1000BASET_LINK_100") (class "Default")
      (node (ref "J3") (pin "19") (pinfunction "19_19") (pintype "passive"))
    )
    (net (code "4") (name "1.1000BASET_LINK_1000") (class "Default")
      (node (ref "J3") (pin "17") (pinfunction "17_17") (pintype "passive"))
      (node (ref "R27") (pin "2") (pinfunction "2_2") (pintype "passive"))
    )
    (net (code "5") (name "1.1000BASET_LINK_ACT") (class "Default")
      (node (ref "J3") (pin "15") (pinfunction "15_15") (pintype "passive"))
      (node (ref "R26") (pin "2") (pinfunction "2_2") (pintype "passive"))
    )
    (net (code "6") (name "1.1000BASET_TR0_N") (class "Default")
      (node (ref "J1") (pin "10") (pinfunction "TRD0-_10") (pintype "bidirectional"))
      (node (ref "J3") (pin "10") (pinfunction "10_10") (pintype "passive"))
      (node (ref "U4") (pin "4") (pinfunction "P3_4") (pintype "passive"))
      (node (ref "U4") (pin "7") (pinfunction "P3_7") (pintype "passive"))
    )
    (net (code "7") (name "1.1000BASET_TR0_P") (class "Default")
      (node (ref "J1") (pin "11") (pinfunction "TRD0+_11") (pintype "bidirectional"))
      (node (ref "J3") (pin "12") (pinfunction "12_12") (pintype "passive"))
      (node (ref "U4") (pin "5") (pinfunction "P4_5") (pintype "passive"))
      (node (ref "U4") (pin "6") (pinfunction "P4_6") (pintype "passive"))
    )
    (net (code "8") (name "1.1000BASET_TR1_N") (class "Default")
      (node (ref "J1") (pin "5") (pinfunction "TRD1-_5") (pintype "bidirectional"))
      (node (ref "J3") (pin "6") (pinfunction "6_6") (pintype "passive"))
      (node (ref "U4") (pin "1") (pinfunction "P1_1") (pintype "passive"))
      (node (ref "U4") (pin "10") (pinfunction "P1_10") (pintype "passive"))
    )
    (net (code "9") (name "1.1000BASET_TR1_P") (class "Default")
      (node (ref "J1") (pin "4") (pinfunction "TRD1+_4") (pintype "bidirectional"))
      (node (ref "J3") (pin "4") (pinfunction "4_4") (pintype "passive"))
      (node (ref "U4") (pin "2") (pinfunction "P2_2") (pintype "passive"))
      (node (ref "U4") (pin "9") (pinfunction "P2_9") (pintype "passive"))
    )
    (net (code "10") (name "1.1000BASET_TR2_N") (class "Default")
      (node (ref "J1") (pin "2") (pinfunction "TRD2-_2") (pintype "bidirectional"))
      (node (ref "J3") (pin "9") (pinfunction "9_9") (pintype "passive"))
      (node (ref "U3") (pin "4") (pinfunction "P3_4") (pintype "passive"))
      (node (ref "U3") (pin "7") (pinfunction "P3_7") (pintype "passive"))
    )
    (net (code "11") (name "1.1000BASET_TR2_P") (class "Default")
      (node (ref "J1") (pin "3") (pinfunction "TRD2+_3") (pintype "bidirectional"))
      (node (ref "J3") (pin "11") (pinfunction "11_11") (pintype "passive"))
      (node (ref "U3") (pin "5") (pinfunction "P4_5") (pintype "passive"))
      (node (ref "U3") (pin "6") (pinfunction "P4_6") (pintype "passive"))
    )
    (net (code "12") (name "1.1000BASET_TR3_N") (class "Default")
      (node (ref "J1") (pin "9") (pinfunction "TRD3-_9") (pintype "bidirectional"))
      (node (ref "J3") (pin "5") (pinfunction "5_5") (pintype "passive"))
      (node (ref "U3") (pin "1") (pinfunction "P1_1") (pintype "passive"))
      (node (ref "U3") (pin "10") (pinfunction "P1_10") (pintype "passive"))
    )
    (net (code "13") (name "1.1000BASET_TR3_P") (class "Default")
      (node (ref "J1") (pin "8") (pinfunction "TRD3+_8") (pintype "bidirectional"))
      (node (ref "J3") (pin "3") (pinfunction "3_3") (pintype "passive"))
      (node (ref "U3") (pin "2") (pinfunction "P2_2") (pintype "passive"))
      (node (ref "U3") (pin "9") (pinfunction "P2_9") (pintype "passive"))
    )
    (net (code "14") (name "1.AUDIO_ACLKX") (class "Default")
      (node (ref "J3") (pin "49") (pinfunction "49_49") (pintype "passive"))
      (node (ref "M1") (pin "4") (pinfunction "BCLK_4") (pintype "input"))
    )
    (net (code "15") (name "1.AUDIO_AXR0") (class "Default")
      (node (ref "J3") (pin "25") (pinfunction "25_25") (pintype "passive"))
    )
    (net (code "16") (name "1.AUDIO_AXR1") (class "Default")
      (node (ref "J3") (pin "27") (pinfunction "27_27") (pintype "passive"))
      (node (ref "R5") (pin "1") (pinfunction "1_1") (pintype "passive"))
    )
    (net (code "17") (name "1.AUDIO_FSX") (class "Default")
      (node (ref "J3") (pin "26") (pinfunction "26_26") (pintype "passive"))
      (node (ref "M1") (pin "1") (pinfunction "WS_1") (pintype "input"))
    )
    (net (code "18") (name "1.CAM1_C_N") (class "Default")
      (node (ref "J2") (pin "27") (pinfunction "27_27") (pintype "passive"))
      (node (ref "J4") (pin "1_8") (pinfunction "8_1_8") (pintype "passive"))
    )
    (net (code "19") (name "1.CAM1_C_P") (class "Default")
      (node (ref "J2") (pin "29") (pinfunction "29_29") (pintype "passive"))
      (node (ref "J4") (pin "1_9") (pinfunction "9_1_9") (pintype "passive"))
    )
    (net (code "20") (name "1.CAM1_D1_N") (class "Default")
      (node (ref "J2") (pin "15") (pinfunction "15_15") (pintype "passive"))
      (node (ref "J4") (pin "1_2") (pinfunction "2_1_2") (pintype "passive"))
    )
    (net (code "21") (name "1.CAM1_D1_P") (class "Default")
      (node (ref "J2") (pin "17") (pinfunction "17_17") (pintype "passive"))
      (node (ref "J4") (pin "1_3") (pinfunction "3_1_3") (pintype "passive"))
    )
    (net (code "22") (name "1.CAM1_D2_N") (class "Default")
      (node (ref "J2") (pin "21") (pinfunction "21_21") (pintype "passive"))
      (node (ref "J4") (pin "1_5") (pinfunction "5_1_5") (pintype "passive"))
    )
    (net (code "23") (name "1.CAM1_D2_P") (class "Default")
      (node (ref "J2") (pin "23") (pinfunction "23_23") (pintype "passive"))
      (node (ref "J4") (pin "1_6") (pinfunction "6_1_6") (pintype "passive"))
    )
    (net (code "24") (name "1.CAM1_D3_N") (class "Default")
      (node (ref "J2") (pin "33") (pinfunction "33_33") (pintype "passive"))
    )
    (net (code "25") (name "1.CAM1_D3_P") (class "Default")
      (node (ref "J2") (pin "35") (pinfunction "35_35") (pintype "passive"))
    )
    (net (code "26") (name "1.CAM1_D4_N") (class "Default")
      (node (ref "J2") (pin "39") (pinfunction "39_39") (pintype "passive"))
    )
    (net (code "27") (name "1.CAM1_D4_P") (class "Default")
      (node (ref "J2") (pin "41") (pinfunction "41_41") (pintype "passive"))
    )
    (net (code "28") (name "1.GPIO_CAMERA_GPIO") (class "Default")
      (node (ref "J3") (pin "97") (pinfunction "97_97") (pintype "passive"))
      (node (ref "J4") (pin "1_11") (pinfunction "11_1_11") (pintype "passive"))
    )
    (net (code "29") (name "1.PCIE_CLKREQ_GPIO") (class "Default")
      (node (ref "J2") (pin "2") (pinfunction "2_2") (pintype "passive"))
      (node (ref "Q2") (pin "3") (pinfunction "D_3") (pintype "passive"))
      (node (ref "R47") (pin "2") (pinfunction "2_2") (pintype "passive"))
      (node (ref "R9") (pin "2") (pinfunction "2_2") (pintype "passive"))
    )
    (net (code "30") (name "1.PCIE_CLK_N") (class "Default")
      (node (ref "J2") (pin "12") (pinfunction "12_12") (pintype "passive"))
      (node (ref "R16") (pin "1") (pinfunction "1_1") (pintype "passive"))
    )
    (net (code "31") (name "1.PCIE_CLK_P") (class "Default")
      (node (ref "J2") (pin "10") (pinfunction "10_10") (pintype "passive"))
      (node (ref "R17") (pin "1") (pinfunction "1_1") (pintype "passive"))
    )
    (net (code "32") (name "1.PCIE_RX0_N") (class "Default")
      (node (ref "J2") (pin "18") (pinfunction "18_18") (pintype "passive"))
      (node (ref "R24") (pin "1") (pinfunction "1_1") (pintype "passive"))
    )
    (net (code "33") (name "1.PCIE_RX0_P") (class "Default")
      (node (ref "J2") (pin "16") (pinfunction "16_16") (pintype "passive"))
      (node (ref "R25") (pin "1") (pinfunction "1_1") (pintype "passive"))
    )
    (net (code "34") (name "1.PCIE_TX0_N") (class "Default")
      (node (ref "J2") (pin "24") (pinfunction "24_24") (pintype "passive"))
      (node (ref "R18") (pin "1") (pinfunction "1_1") (pintype "passive"))
    )
    (net (code "35") (name "1.PCIE_TX0_P") (class "Default")
      (node (ref "J2") (pin "22") (pinfunction "22_22") (pintype "passive"))
      (node (ref "R23") (pin "1") (pinfunction "1_1") (pintype "passive"))
    )
    (net (code "36") (name "1.PCIE__CLK_N") (class "Default")
      (node (ref "R16") (pin "2") (pinfunction "2_2") (pintype "passive"))
      (node (ref "R31") (pin "2") (pinfunction "2_2") (pintype "passive"))
      (node (ref "U5") (pin "10") (pinfunction "PCIE_REFCLK_N_10") (pintype "bidirectional"))
    )
    (net (code "37") (name "1.PCIE__CLK_P") (class "Default")
      (node (ref "R17") (pin "2") (pinfunction "2_2") (pintype "passive"))
      (node (ref "R32") (pin "2") (pinfunction "2_2") (pintype "passive"))
      (node (ref "U5") (pin "11") (pinfunction "PCIE_REFCLK_P_11") (pintype "bidirectional"))
    )
    (net (code "38") (name "1.USB_OTG_ID") (class "Default")
      (node (ref "J2") (pin "1") (pinfunction "1_1") (pintype "passive"))
      (node (ref "R13") (pin "1") (pinfunction "1_1") (pintype "passive"))
    )
    (net (code "39") (name "1.VLOGIC_VLOGIC") (class "Default")
      (node (ref "R54") (pin "1") (pinfunction "1_1") (pintype "passive"))
      (node (ref "R9") (pin "1") (pinfunction "1_1") (pintype "passive"))
    )
    (net (code "40") (name "3.3.3V_VCC_3.3") (class "Default")
      (node (ref "C15") (pin "1") (pinfunction "1_1") (pintype "passive"))
      (node (ref "C2") (pin "1") (pinfunction "1_1") (pintype "passive"))
      (node (ref "C4") (pin "1") (pinfunction "1_1") (pintype "passive"))
      (node (ref "C5") (pin "1") (pinfunction "1_1") (pintype "passive"))
      (node (ref "C6") (pin "1") (pinfunction "1_1") (pintype "passive"))
      (node (ref "J1") (pin "18") (pinfunction "LED1_G+Y-_18") (pintype "bidirectional"))
      (node (ref "J1") (pin "19") (pinfunction "LED2_G-Y+_19") (pintype "bidirectional"))
      (node (ref "J4") (pin "1_15") (pinfunction "15_1_15") (pintype "passive"))
      (node (ref "L1") (pin "2") (pinfunction "2_2") (pintype "passive"))
      (node (ref "M1") (pin "5") (pinfunction "VDD_5") (pintype "power_in"))
      (node (ref "Q5") (pin "2") (pinfunction "S_2") (pintype "passive"))
      (node (ref "R1") (pin "2") (pinfunction "2_2") (pintype "passive"))
      (node (ref "R3") (pin "2") (pinfunction "2_2") (pintype "passive"))
      (node (ref "R35") (pin "2") (pinfunction "2_2") (pintype "passive"))
      (node (ref "R42") (pin "2") (pinfunction "2_2") (pintype "passive"))
      (node (ref "R43") (pin "1") (pinfunction "1_1") (pintype "passive"))
      (node (ref "R61") (pin "2") (pinfunction "2_2") (pintype "passive"))
      (node (ref "U7") (pin "1") (pinfunction "VIN_1") (pintype "power_in"))
      (node (ref "U7") (pin "3") (pinfunction "CONTROL_3") (pintype "input"))
    )
    (net (code "41") (name "3.3V") (class "Default")
      (node (ref "C27") (pin "1") (pinfunction "1_1") (pintype "passive"))
      (node (ref "C28") (pin "1") (pinfunction "1_1") (pintype "passive"))
      (node (ref "Q5") (pin "3") (pinfunction "D_3") (pintype "passive"))
      (node (ref "R38") (pin "2") (pinfunction "2_2") (pintype "passive"))
      (node (ref "R39") (pin "1") (pinfunction "1_1") (pintype "passive"))
      (node (ref "R42") (pin "1") (pinfunction "1_1") (pintype "passive"))
      (node (ref "R46") (pin "2") (pinfunction "2_2") (pintype "passive"))
      (node (ref "U5") (pin "56") (pinfunction "VIN_56") (pintype "bidirectional"))
      (node (ref "U5") (pin "57") (pinfunction "VIN_57") (pintype "bidirectional"))
      (node (ref "U5") (pin "58") (pinfunction "VIN_58") (pintype "bidirectional"))
      (node (ref "U5") (pin "59") (pinfunction "VIN_59") (pintype "bidirectional"))
      (node (ref "U5") (pin "60") (pinfunction "VIN_60") (pintype "bidirectional"))
      (node (ref "U5") (pin "61") (pinfunction "VIN_61") (pintype "bidirectional"))
      (node (ref "U5") (pin "62") (pinfunction "VIN_62") (pintype "bidirectional"))
      (node (ref "U5") (pin "63") (pinfunction "VIN_63") (pintype "bidirectional"))
      (node (ref "U5") (pin "64") (pinfunction "VIN_64") (pintype "bidirectional"))
      (node (ref "U5") (pin "65") (pinfunction "VIN_65") (pintype "bidirectional"))
      (node (ref "U5") (pin "66") (pinfunction "VIN_66") (pintype "bidirectional"))
      (node (ref "U5") (pin "67") (pinfunction "VIN_67") (pintype "bidirectional"))
    )
    (net (code "42") (name "3.3V_OUT$1") (class "Default")
      (node (ref "J3") (pin "84") (pinfunction "84_84") (pintype "passive"))
      (node (ref "J3") (pin "86") (pinfunction "86_86") (pintype "passive"))
      (node (ref "Q4") (pin "3") (pinfunction "D_3") (pintype "passive"))
      (node (ref "R52") (pin "1") (pinfunction "1_1") (pintype "passive"))
    )
    (net (code "43") (name "3.3V_SWITCH$1") (class "Default")
      (node (ref "Q3") (pin "3") (pinfunction "D_3") (pintype "passive"))
      (node (ref "R54") (pin "2") (pinfunction "2_2") (pintype "passive"))
    )
    (net (code "44") (name "5.5.0V_VCC_5.0") (class "Default")
      (node (ref "C1") (pin "1") (pinfunction "1_1") (pintype "passive"))
      (node (ref "C18") (pin "1") (pinfunction "1_1") (pintype "passive"))
      (node (ref "C3") (pin "1") (pinfunction "1_1") (pintype "passive"))
      (node (ref "C44") (pin "1") (pinfunction "1_1") (pintype "passive"))
      (node (ref "IC1") (pin "2") (pinfunction "VIN_2") (pintype "power_in"))
      (node (ref "IC1") (pin "3") (pinfunction "VIN_3") (pintype "power_in"))
      (node (ref "IC1") (pin "4") (pinfunction "EN_4") (pintype "input"))
      (node (ref "IC1") (pin "8") (pinfunction "VIN_8") (pintype "power_in"))
      (node (ref "J3") (pin "77") (pinfunction "77_77") (pintype "passive"))
      (node (ref "J3") (pin "79") (pinfunction "79_79") (pintype "passive"))
      (node (ref "J3") (pin "81") (pinfunction "81_81") (pintype "passive"))
      (node (ref "J3") (pin "83") (pinfunction "83_83") (pintype "passive"))
      (node (ref "J3") (pin "85") (pinfunction "85_85") (pintype "passive"))
      (node (ref "J3") (pin "87") (pinfunction "87_87") (pintype "passive"))
      (node (ref "L2") (pin "2") (pinfunction "2_2") (pintype "passive"))
    )
    (net (code "45") (name "AON") (class "Default")
      (node (ref "C34") (pin "1") (pinfunction "1_1") (pintype "passive"))
      (node (ref "R37") (pin "2") (pinfunction "2_2") (pintype "passive"))
      (node (ref "R38") (pin "1") (pinfunction "1_1") (pintype "passive"))
      (node (ref "U5") (pin "54") (pinfunction "AON_54") (pintype "bidirectional"))
    )
    (net (code "46") (name "COMMON_SHIELD") (class "Default")
      (node (ref "J1") (pin "SHIELD1") (pinfunction "COMMON_SHIELD_SHIELD1") (pintype "bidirectional"))
      (node (ref "J1") (pin "SHIELD2") (pinfunction "COMMON_SHIELD_SHIELD2") (pintype "bidirectional"))
      (node (ref "U3") (pin "3") (pinfunction "SHIELD_3") (pintype "passive"))
      (node (ref "U3") (pin "8") (pinfunction "SHIELD_8") (pintype "passive"))
      (node (ref "U4") (pin "3") (pinfunction "SHIELD_3") (pintype "passive"))
      (node (ref "U4") (pin "8") (pinfunction "SHIELD_8") (pintype "passive"))
    )
    (net (code "47") (name "CORAL_D_N") (class "Default")
      (node (ref "J2") (pin "5") (pinfunction "5_5") (pintype "passive"))
      (node (ref "R14") (pin "1") (pinfunction "1_1") (pintype "passive"))
    )
    (net (code "48") (name "CORAL_D_P") (class "Default")
      (node (ref "J2") (pin "3") (pinfunction "3_3") (pintype "passive"))
      (node (ref "R12") (pin "1") (pinfunction "1_1") (pintype "passive"))
    )
    (net (code "49") (name "CT0$5") (class "Default")
      (node (ref "J1") (pin "13") (pinfunction "JCT0_13") (pintype "bidirectional"))
      (node (ref "U2") (pin "1") (pinfunction "VA1_1") (pintype "bidirectional"))
    )
    (net (code "50") (name "CT1$5") (class "Default")
      (node (ref "J1") (pin "14") (pinfunction "JCT1_14") (pintype "bidirectional"))
      (node (ref "U2") (pin "2") (pinfunction "VA2_2") (pintype "bidirectional"))
    )
    (net (code "51") (name "CT2$5") (class "Default")
      (node (ref "J1") (pin "15") (pinfunction "JCT2_15") (pintype "bidirectional"))
      (node (ref "U2") (pin "3") (pinfunction "VB1_3") (pintype "bidirectional"))
    )
    (net (code "52") (name "CT3$5") (class "Default")
      (node (ref "J1") (pin "16") (pinfunction "JCT3_16") (pintype "bidirectional"))
      (node (ref "U2") (pin "4") (pinfunction "VB2_4") (pintype "bidirectional"))
    )
    (net (code "53") (name "EEPROM_~{WP}") (class "Default")
      (node (ref "J3") (pin "20") (pinfunction "20_20") (pintype "passive"))
    )
    (net (code "54") (name "ETH_SYNC_IN") (class "Default")
      (node (ref "J3") (pin "16") (pinfunction "16_16") (pintype "passive"))
    )
    (net (code "55") (name "ETH_SYNC_OUT") (class "Default")
      (node (ref "J3") (pin "18") (pinfunction "18_18") (pintype "passive"))
    )
    (net (code "56") (name "FB_3.3$3") (class "Default")
      (node (ref "C4") (pin "2") (pinfunction "2_2") (pintype "passive"))
      (node (ref "IC1") (pin "10") (pinfunction "FB_10") (pintype "output"))
      (node (ref "R61") (pin "1") (pinfunction "1_1") (pintype "passive"))
      (node (ref "R62") (pin "2") (pinfunction "2_2") (pintype "passive"))
    )
    (net (code "57") (name "GLOBAL_EN") (class "Default")
      (node (ref "J3") (pin "99") (pinfunction "99_99") (pintype "passive"))
    )
    (net (code "58") (name "GND") (class "Default")
      (node (ref "C1") (pin "2") (pinfunction "2_2") (pintype "passive"))
      (node (ref "C10") (pin "-") (pinfunction "2_-") (pintype "passive"))
      (node (ref "C15") (pin "2") (pinfunction "2_2") (pintype "passive"))
      (node (ref "C16") (pin "2") (pinfunction "2_2") (pintype "passive"))
      (node (ref "C17") (pin "2") (pinfunction "2_2") (pintype "passive"))
      (node (ref "C18") (pin "2") (pinfunction "2_2") (pintype "passive"))
      (node (ref "C2") (pin "2") (pinfunction "2_2") (pintype "passive"))
      (node (ref "C24") (pin "2") (pinfunction "2_2") (pintype "passive"))
      (node (ref "C27") (pin "2") (pinfunction "2_2") (pintype "passive"))
      (node (ref "C28") (pin "2") (pinfunction "2_2") (pintype "passive"))
      (node (ref "C3") (pin "2") (pinfunction "2_2") (pintype "passive"))
      (node (ref "C34") (pin "2") (pinfunction "2_2") (pintype "passive"))
      (node (ref "C38") (pin "2") (pinfunction "2_2") (pintype "passive"))
      (node (ref "C40") (pin "2") (pinfunction "2_2") (pintype "passive"))
      (node (ref "C41") (pin "2") (pinfunction "2_2") (pintype "passive"))
      (node (ref "C44") (pin "2") (pinfunction "2_2") (pintype "passive"))
      (node (ref "C45") (pin "2") (pinfunction "2_2") (pintype "passive"))
      (node (ref "C5") (pin "2") (pinfunction "2_2") (pintype "passive"))
      (node (ref "C6") (pin "2") (pinfunction "2_2") (pintype "passive"))
      (node (ref "C7") (pin "2") (pinfunction "2_2") (pintype "passive"))
      (node (ref "IC1") (pin "1") (pinfunction "PGND_1") (pintype "power_in"))
      (node (ref "IC1") (pin "11") (pinfunction "GND_11") (pintype "power_in"))
      (node (ref "IC1") (pin "12") (pinfunction "GND_12") (pintype "power_in"))
      (node (ref "IC1") (pin "16") (pinfunction "PGND_16") (pintype "power_in"))
      (node (ref "IC1") (pin "5") (pinfunction "SYNC_5") (pintype "input"))
      (node (ref "IC1") (pin "6") (pinfunction "LBO_6") (pintype "passive"))
      (node (ref "IC1") (pin "7") (pinfunction "LBI_7") (pintype "input"))
      (node (ref "IC1") (pin "9") (pinfunction "GND_9") (pintype "power_in"))
      (node (ref "IC1") (pin "P$1") (pinfunction "GND_P$1") (pintype "power_in"))
      (node (ref "IC2") (pin "4") (pinfunction "GND_4") (pintype "power_in"))
      (node (ref "IC2") (pin "7") (pinfunction "WP_7") (pintype "input"))
      (node (ref "J2") (pin "13") (pinfunction "13_13") (pintype "passive"))
      (node (ref "J2") (pin "14") (pinfunction "14_14") (pintype "passive"))
      (node (ref "J2") (pin "19") (pinfunction "19_19") (pintype "passive"))
      (node (ref "J2") (pin "20") (pinfunction "20_20") (pintype "passive"))
      (node (ref "J2") (pin "25") (pinfunction "25_25") (pintype "passive"))
      (node (ref "J2") (pin "26") (pinfunction "26_26") (pintype "passive"))
      (node (ref "J2") (pin "31") (pinfunction "31_31") (pintype "passive"))
      (node (ref "J2") (pin "32") (pinfunction "32_32") (pintype "passive"))
      (node (ref "J2") (pin "37") (pinfunction "37_37") (pintype "passive"))
      (node (ref "J2") (pin "38") (pinfunction "38_38") (pintype "passive"))
      (node (ref "J2") (pin "44") (pinfunction "44_44") (pintype "passive"))
      (node (ref "J2") (pin "50") (pinfunction "50_50") (pintype "passive"))
      (node (ref "J2") (pin "55") (pinfunction "55_55") (pintype "passive"))
      (node (ref "J2") (pin "56") (pinfunction "56_56") (pintype "passive"))
      (node (ref "J2") (pin "61") (pinfunction "61_61") (pintype "passive"))
      (node (ref "J2") (pin "62") (pinfunction "62_62") (pintype "passive"))
      (node (ref "J2") (pin "67") (pinfunction "67_67") (pintype "passive"))
      (node (ref "J2") (pin "68") (pinfunction "68_68") (pintype "passive"))
      (node (ref "J2") (pin "7") (pinfunction "7_7") (pintype "passive"))
      (node (ref "J2") (pin "73") (pinfunction "73_73") (pintype "passive"))
      (node (ref "J2") (pin "74") (pinfunction "74_74") (pintype "passive"))
      (node (ref "J2") (pin "79") (pinfunction "79_79") (pintype "passive"))
      (node (ref "J2") (pin "8") (pinfunction "8_8") (pintype "passive"))
      (node (ref "J2") (pin "80") (pinfunction "80_80") (pintype "passive"))
      (node (ref "J2") (pin "85") (pinfunction "85_85") (pintype "passive"))
      (node (ref "J2") (pin "86") (pinfunction "86_86") (pintype "passive"))
      (node (ref "J2") (pin "91") (pinfunction "91_91") (pintype "passive"))
      (node (ref "J2") (pin "92") (pinfunction "92_92") (pintype "passive"))
      (node (ref "J2") (pin "97") (pinfunction "97_97") (pintype "passive"))
      (node (ref "J2") (pin "98") (pinfunction "98_98") (pintype "passive"))
      (node (ref "J3") (pin "1") (pinfunction "1_1") (pintype "passive"))
      (node (ref "J3") (pin "13") (pinfunction "13_13") (pintype "passive"))
      (node (ref "J3") (pin "14") (pinfunction "14_14") (pintype "passive"))
      (node (ref "J3") (pin "2") (pinfunction "2_2") (pintype "passive"))
      (node (ref "J3") (pin "22") (pinfunction "22_22") (pintype "passive"))
      (node (ref "J3") (pin "23") (pinfunction "23_23") (pintype "passive"))
      (node (ref "J3") (pin "32") (pinfunction "32_32") (pintype "passive"))
      (node (ref "J3") (pin "33") (pinfunction "33_33") (pintype "passive"))
      (node (ref "J3") (pin "42") (pinfunction "42_42") (pintype "passive"))
      (node (ref "J3") (pin "43") (pinfunction "43_43") (pintype "passive"))
      (node (ref "J3") (pin "52") (pinfunction "52_52") (pintype "passive"))
      (node (ref "J3") (pin "53") (pinfunction "53_53") (pintype "passive"))
      (node (ref "J3") (pin "59") (pinfunction "59_59") (pintype "passive"))
      (node (ref "J3") (pin "60") (pinfunction "60_60") (pintype "passive"))
      (node (ref "J3") (pin "65") (pinfunction "65_65") (pintype "passive"))
      (node (ref "J3") (pin "66") (pinfunction "66_66") (pintype "passive"))
      (node (ref "J3") (pin "7") (pinfunction "7_7") (pintype "passive"))
      (node (ref "J3") (pin "71") (pinfunction "71_71") (pintype "passive"))
      (node (ref "J3") (pin "74") (pinfunction "74_74") (pintype "passive"))
      (node (ref "J3") (pin "8") (pinfunction "8_8") (pintype "passive"))
      (node (ref "J3") (pin "98") (pinfunction "98_98") (pintype "passive"))
      (node (ref "J4") (pin "1_1") (pinfunction "1_1_1") (pintype "passive"))
      (node (ref "J4") (pin "1_10") (pinfunction "10_1_10") (pintype "passive"))
      (node (ref "J4") (pin "1_4") (pinfunction "4_1_4") (pintype "passive"))
      (node (ref "J4") (pin "1_7") (pinfunction "7_1_7") (pintype "passive"))
      (node (ref "M1") (pin "3") (pinfunction "GND_3") (pintype "power_in"))
      (node (ref "MP1") (pin "1") (pinfunction "TP_1") (pintype "bidirectional"))
      (node (ref "MP2") (pin "1") (pinfunction "TP_1") (pintype "bidirectional"))
      (node (ref "MP3") (pin "1") (pinfunction "TP_1") (pintype "bidirectional"))
      (node (ref "MP4") (pin "1") (pinfunction "TP_1") (pintype "bidirectional"))
      (node (ref "Q1") (pin "2") (pinfunction "S_2") (pintype "passive"))
      (node (ref "Q6") (pin "2") (pinfunction "S_2") (pintype "passive"))
      (node (ref "R11") (pin "1") (pinfunction "1_1") (pintype "passive"))
      (node (ref "R13") (pin "2") (pinfunction "2_2") (pintype "passive"))
      (node (ref "R2") (pin "1") (pinfunction "1_1") (pintype "passive"))
      (node (ref "R20") (pin "1") (pinfunction "1_1") (pintype "passive"))
      (node (ref "R30") (pin "1") (pinfunction "1_1") (pintype "passive"))
      (node (ref "R31") (pin "1") (pinfunction "1_1") (pintype "passive"))
      (node (ref "R32") (pin "1") (pinfunction "1_1") (pintype "passive"))
      (node (ref "R36") (pin "1") (pinfunction "1_1") (pintype "passive"))
      (node (ref "R4") (pin "1") (pinfunction "1_1") (pintype "passive"))
      (node (ref "R44") (pin "2") (pinfunction "2_2") (pintype "passive"))
      (node (ref "R49") (pin "1") (pinfunction "1_1") (pintype "passive"))
      (node (ref "R55") (pin "1") (pinfunction "1_1") (pintype "passive"))
      (node (ref "R6") (pin "1") (pinfunction "1_1") (pintype "passive"))
      (node (ref "R62") (pin "1") (pinfunction "1_1") (pintype "passive"))
      (node (ref "R7") (pin "1") (pinfunction "1_1") (pintype "passive"))
      (node (ref "U2") (pin "7") (pinfunction "-VDC_7") (pintype "bidirectional"))
      (node (ref "U5") (pin "1") (pinfunction "GND_1") (pintype "bidirectional"))
      (node (ref "U5") (pin "100") (pinfunction "GND_100") (pintype "bidirectional"))
      (node (ref "U5") (pin "101") (pinfunction "GND_101") (pintype "bidirectional"))
      (node (ref "U5") (pin "102") (pinfunction "GND_102") (pintype "bidirectional"))
      (node (ref "U5") (pin "103") (pinfunction "GND_103") (pintype "bidirectional"))
      (node (ref "U5") (pin "104") (pinfunction "GND_104") (pintype "bidirectional"))
      (node (ref "U5") (pin "105") (pinfunction "GND_105") (pintype "bidirectional"))
      (node (ref "U5") (pin "106") (pinfunction "GND_106") (pintype "bidirectional"))
      (node (ref "U5") (pin "107") (pinfunction "GND_107") (pintype "bidirectional"))
      (node (ref "U5") (pin "108") (pinfunction "GND_108") (pintype "bidirectional"))
      (node (ref "U5") (pin "109") (pinfunction "GND_109") (pintype "bidirectional"))
      (node (ref "U5") (pin "110") (pinfunction "GND_110") (pintype "bidirectional"))
      (node (ref "U5") (pin "111") (pinfunction "GND_111") (pintype "bidirectional"))
      (node (ref "U5") (pin "112") (pinfunction "GND_112") (pintype "bidirectional"))
      (node (ref "U5") (pin "113") (pinfunction "GND_113") (pintype "bidirectional"))
      (node (ref "U5") (pin "114") (pinfunction "GND_114") (pintype "bidirectional"))
      (node (ref "U5") (pin "115") (pinfunction "GND_115") (pintype "bidirectional"))
      (node (ref "U5") (pin "116") (pinfunction "GND_116") (pintype "bidirectional"))
      (node (ref "U5") (pin "117") (pinfunction "GND_117") (pintype "bidirectional"))
      (node (ref "U5") (pin "118") (pinfunction "GND_118") (pintype "bidirectional"))
      (node (ref "U5") (pin "119") (pinfunction "GND_119") (pintype "bidirectional"))
      (node (ref "U5") (pin "12") (pinfunction "GND_12") (pintype "bidirectional"))
      (node (ref "U5") (pin "120") (pinfunction "GND_120") (pintype "bidirectional"))
      (node (ref "U5") (pin "15") (pinfunction "GND_15") (pintype "bidirectional"))
      (node (ref "U5") (pin "16") (pinfunction "GND_16") (pintype "bidirectional"))
      (node (ref "U5") (pin "17") (pinfunction "GND_17") (pintype "bidirectional"))
      (node (ref "U5") (pin "18") (pinfunction "GND_18") (pintype "bidirectional"))
      (node (ref "U5") (pin "19") (pinfunction "GND_19") (pintype "bidirectional"))
      (node (ref "U5") (pin "2") (pinfunction "GND_2") (pintype "bidirectional"))
      (node (ref "U5") (pin "20") (pinfunction "GND_20") (pintype "bidirectional"))
      (node (ref "U5") (pin "21") (pinfunction "GND_21") (pintype "bidirectional"))
      (node (ref "U5") (pin "22") (pinfunction "GND_22") (pintype "bidirectional"))
      (node (ref "U5") (pin "23") (pinfunction "GND_23") (pintype "bidirectional"))
      (node (ref "U5") (pin "24") (pinfunction "GND_24") (pintype "bidirectional"))
      (node (ref "U5") (pin "25") (pinfunction "GND_25") (pintype "bidirectional"))
      (node (ref "U5") (pin "26") (pinfunction "GND_26") (pintype "bidirectional"))
      (node (ref "U5") (pin "27") (pinfunction "GND_27") (pintype "bidirectional"))
      (node (ref "U5") (pin "28") (pinfunction "GND_28") (pintype "bidirectional"))
      (node (ref "U5") (pin "29") (pinfunction "GND_29") (pintype "bidirectional"))
      (node (ref "U5") (pin "3") (pinfunction "GND_3") (pintype "bidirectional"))
      (node (ref "U5") (pin "30") (pinfunction "GND_30") (pintype "bidirectional"))
      (node (ref "U5") (pin "31") (pinfunction "GND_31") (pintype "bidirectional"))
      (node (ref "U5") (pin "32") (pinfunction "GND_32") (pintype "bidirectional"))
      (node (ref "U5") (pin "33") (pinfunction "GND_33") (pintype "bidirectional"))
      (node (ref "U5") (pin "34") (pinfunction "GND_34") (pintype "bidirectional"))
      (node (ref "U5") (pin "35") (pinfunction "GND_35") (pintype "bidirectional"))
      (node (ref "U5") (pin "36") (pinfunction "GND_36") (pintype "bidirectional"))
      (node (ref "U5") (pin "38") (pinfunction "GND_38") (pintype "bidirectional"))
      (node (ref "U5") (pin "39") (pinfunction "GND_39") (pintype "bidirectional"))
      (node (ref "U5") (pin "40") (pinfunction "GND_40") (pintype "bidirectional"))
      (node (ref "U5") (pin "41") (pinfunction "GND_41") (pintype "bidirectional"))
      (node (ref "U5") (pin "42") (pinfunction "GND_42") (pintype "bidirectional"))
      (node (ref "U5") (pin "43") (pinfunction "GND_43") (pintype "bidirectional"))
      (node (ref "U5") (pin "44") (pinfunction "GND_44") (pintype "bidirectional"))
      (node (ref "U5") (pin "45") (pinfunction "GND_45") (pintype "bidirectional"))
      (node (ref "U5") (pin "46") (pinfunction "GND_46") (pintype "bidirectional"))
      (node (ref "U5") (pin "47") (pinfunction "GND_47") (pintype "bidirectional"))
      (node (ref "U5") (pin "48") (pinfunction "GND_48") (pintype "bidirectional"))
      (node (ref "U5") (pin "51") (pinfunction "GND_51") (pintype "bidirectional"))
      (node (ref "U5") (pin "55") (pinfunction "GND_55") (pintype "bidirectional"))
      (node (ref "U5") (pin "6") (pinfunction "GND_6") (pintype "bidirectional"))
      (node (ref "U5") (pin "68") (pinfunction "GND_68") (pintype "bidirectional"))
      (node (ref "U5") (pin "69") (pinfunction "GND_69") (pintype "bidirectional"))
      (node (ref "U5") (pin "70") (pinfunction "GND_70") (pintype "bidirectional"))
      (node (ref "U5") (pin "71") (pinfunction "GND_71") (pintype "bidirectional"))
      (node (ref "U5") (pin "72") (pinfunction "GND_72") (pintype "bidirectional"))
      (node (ref "U5") (pin "73") (pinfunction "GND_73") (pintype "bidirectional"))
      (node (ref "U5") (pin "74") (pinfunction "GND_74") (pintype "bidirectional"))
      (node (ref "U5") (pin "75") (pinfunction "GND_75") (pintype "bidirectional"))
      (node (ref "U5") (pin "79") (pinfunction "GND_79") (pintype "bidirectional"))
      (node (ref "U5") (pin "80") (pinfunction "GND_80") (pintype "bidirectional"))
      (node (ref "U5") (pin "81") (pinfunction "GND_81") (pintype "bidirectional"))
      (node (ref "U5") (pin "86") (pinfunction "GND_86") (pintype "bidirectional"))
      (node (ref "U5") (pin "87") (pinfunction "GND_87") (pintype "bidirectional"))
      (node (ref "U5") (pin "88") (pinfunction "GND_88") (pintype "bidirectional"))
      (node (ref "U5") (pin "89") (pinfunction "GND_89") (pintype "bidirectional"))
      (node (ref "U5") (pin "9") (pinfunction "GND_9") (pintype "bidirectional"))
      (node (ref "U5") (pin "90") (pinfunction "GND_90") (pintype "bidirectional"))
      (node (ref "U5") (pin "91") (pinfunction "GND_91") (pintype "bidirectional"))
      (node (ref "U5") (pin "92") (pinfunction "GND_92") (pintype "bidirectional"))
      (node (ref "U5") (pin "93") (pinfunction "GND_93") (pintype "bidirectional"))
      (node (ref "U5") (pin "94") (pinfunction "GND_94") (pintype "bidirectional"))
      (node (ref "U5") (pin "95") (pinfunction "GND_95") (pintype "bidirectional"))
      (node (ref "U5") (pin "96") (pinfunction "GND_96") (pintype "bidirectional"))
      (node (ref "U5") (pin "97") (pinfunction "GND_97") (pintype "bidirectional"))
      (node (ref "U5") (pin "98") (pinfunction "GND_98") (pintype "bidirectional"))
      (node (ref "U5") (pin "99") (pinfunction "GND_99") (pintype "bidirectional"))
      (node (ref "U6") (pin "5") (pinfunction "GND_5") (pintype "bidirectional"))
      (node (ref "U6") (pin "EPAD") (pinfunction "GND_EPAD") (pintype "bidirectional"))
      (node (ref "U7") (pin "2") (pinfunction "GND_2") (pintype "power_in"))
    )
    (net (code "59") (name "GPIO_VREF$1") (class "Default")
      (node (ref "C45") (pin "1") (pinfunction "1_1") (pintype "passive"))
      (node (ref "IC2") (pin "8") (pinfunction "VCC_8") (pintype "power_in"))
      (node (ref "J3") (pin "78") (pinfunction "78_78") (pintype "passive"))
      (node (ref "R10") (pin "2") (pinfunction "2_2") (pintype "passive"))
      (node (ref "R51") (pin "2") (pinfunction "2_2") (pintype "passive"))
      (node (ref "R52") (pin "2") (pinfunction "2_2") (pintype "passive"))
      (node (ref "R53") (pin "2") (pinfunction "2_2") (pintype "passive"))
      (node (ref "R8") (pin "1") (pinfunction "1_1") (pintype "passive"))
    )
    (net (code "60") (name "ID_SC$1") (class "Default")
      (node (ref "IC2") (pin "6") (pinfunction "SCL_6") (pintype "bidirectional"))
      (node (ref "J3") (pin "35") (pinfunction "35_35") (pintype "passive"))
      (node (ref "R10") (pin "1") (pinfunction "1_1") (pintype "passive"))
    )
    (net (code "61") (name "ID_SD$1") (class "Default")
      (node (ref "IC2") (pin "5") (pinfunction "SDA_5") (pintype "bidirectional"))
      (node (ref "J3") (pin "36") (pinfunction "36_36") (pintype "passive"))
      (node (ref "R51") (pin "1") (pinfunction "1_1") (pintype "passive"))
    )
    (net (code "62") (name "INTR$2") (class "Default")
      (node (ref "U5") (pin "77") (pinfunction "INTR_77") (pintype "bidirectional"))
    )
    (net (code "63") (name "Net-(C7-Pad1)") (class "Default")
      (node (ref "C7") (pin "1") (pinfunction "1_1") (pintype "passive"))
      (node (ref "R34") (pin "2") (pinfunction "2_2") (pintype "passive"))
      (node (ref "R35") (pin "1") (pinfunction "1_1") (pintype "passive"))
      (node (ref "R36") (pin "2") (pinfunction "2_2") (pintype "passive"))
    )
    (net (code "64") (name "Net-(C10-1)") (class "Default")
      (node (ref "C10") (pin "+") (pinfunction "1_+") (pintype "passive"))
      (node (ref "C17") (pin "1") (pinfunction "1_1") (pintype "passive"))
      (node (ref "L2") (pin "1") (pinfunction "1_1") (pintype "passive"))
      (node (ref "U2") (pin "8") (pinfunction "+VDC_8") (pintype "bidirectional"))
    )
    (net (code "65") (name "Net-(C24-Pad1)") (class "Default")
      (node (ref "C24") (pin "1") (pinfunction "1_1") (pintype "passive"))
      (node (ref "R19") (pin "2") (pinfunction "2_2") (pintype "passive"))
      (node (ref "R22") (pin "2") (pinfunction "2_2") (pintype "passive"))
      (node (ref "R28") (pin "2") (pinfunction "2_2") (pintype "passive"))
      (node (ref "R29") (pin "2") (pinfunction "2_2") (pintype "passive"))
    )
    (net (code "66") (name "Net-(IC2-A0)") (class "Default")
      (node (ref "IC2") (pin "1") (pinfunction "A0_1") (pintype "input"))
      (node (ref "R8") (pin "2") (pinfunction "2_2") (pintype "passive"))
    )
    (net (code "67") (name "Net-(IC2-A1)") (class "Default")
      (node (ref "IC2") (pin "2") (pinfunction "A1_2") (pintype "input"))
      (node (ref "R7") (pin "2") (pinfunction "2_2") (pintype "passive"))
    )
    (net (code "68") (name "Net-(IC2-A2)") (class "Default")
      (node (ref "IC2") (pin "3") (pinfunction "A2_3") (pintype "input"))
      (node (ref "R6") (pin "2") (pinfunction "2_2") (pintype "passive"))
    )
    (net (code "69") (name "Net-(J1-LED1_G-Y+)") (class "Default")
      (node (ref "J1") (pin "17") (pinfunction "LED1_G-Y+_17") (pintype "bidirectional"))
      (node (ref "R26") (pin "1") (pinfunction "1_1") (pintype "passive"))
    )
    (net (code "70") (name "Net-(J1-LED2_G+Y-)") (class "Default")
      (node (ref "J1") (pin "20") (pinfunction "LED2_G+Y-_20") (pintype "bidirectional"))
      (node (ref "R27") (pin "1") (pinfunction "1_1") (pintype "passive"))
    )
    (net (code "71") (name "Net-(M1-DATA_OUT)") (class "Default")
      (node (ref "M1") (pin "6") (pinfunction "DATA_OUT_6") (pintype "output"))
      (node (ref "R5") (pin "2") (pinfunction "2_2") (pintype "passive"))
    )
    (net (code "72") (name "Net-(M1-SELECT)") (class "Default")
      (node (ref "M1") (pin "2") (pinfunction "SELECT_2") (pintype "input"))
      (node (ref "R2") (pin "2") (pinfunction "2_2") (pintype "passive"))
      (node (ref "R3") (pin "1") (pinfunction "1_1") (pintype "passive"))
    )
    (net (code "73") (name "Net-(Q1-D)") (class "Default")
      (node (ref "Q1") (pin "3") (pinfunction "D_3") (pintype "passive"))
      (node (ref "Q3") (pin "1") (pinfunction "G_1") (pintype "passive"))
      (node (ref "Q4") (pin "1") (pinfunction "G_1") (pintype "passive"))
      (node (ref "Q7") (pin "1") (pinfunction "G_1") (pintype "passive"))
      (node (ref "Q8") (pin "1") (pinfunction "G_1") (pintype "passive"))
    )
    (net (code "74") (name "Net-(Q3-S)") (class "Default")
      (node (ref "Q3") (pin "2") (pinfunction "S_2") (pintype "passive"))
      (node (ref "Q4") (pin "2") (pinfunction "S_2") (pintype "passive"))
    )
    (net (code "75") (name "Net-(Q5-G)") (class "Default")
      (node (ref "Q5") (pin "1") (pinfunction "G_1") (pintype "passive"))
      (node (ref "Q6") (pin "3") (pinfunction "D_3") (pintype "passive"))
      (node (ref "R43") (pin "2") (pinfunction "2_2") (pintype "passive"))
    )
    (net (code "76") (name "Net-(Q7-S)") (class "Default")
      (node (ref "Q7") (pin "2") (pinfunction "S_2") (pintype "passive"))
      (node (ref "Q8") (pin "2") (pinfunction "S_2") (pintype "passive"))
    )
    (net (code "77") (name "Net-(S1-A')") (class "Default")
      (node (ref "R11") (pin "2") (pinfunction "2_2") (pintype "passive"))
      (node (ref "S1") (pin "1") (pinfunction "A_1") (pintype "passive"))
      (node (ref "S1") (pin "2") (pinfunction "A'_2") (pintype "passive"))
    )
    (net (code "78") (name "Net-(U5-USB2_D_N)") (class "Default")
      (node (ref "R14") (pin "2") (pinfunction "2_2") (pintype "passive"))
      (node (ref "U5") (pin "14") (pinfunction "USB2_D_N_14") (pintype "bidirectional"))
    )
    (net (code "79") (name "Net-(U5-USB2_D_P)") (class "Default")
      (node (ref "R12") (pin "2") (pinfunction "2_2") (pintype "passive"))
      (node (ref "U5") (pin "13") (pinfunction "USB2_D_P_13") (pintype "bidirectional"))
    )
    (net (code "80") (name "Net-(U6-CT)") (class "Default")
      (node (ref "C41") (pin "1") (pinfunction "1_1") (pintype "passive"))
      (node (ref "U6") (pin "3") (pinfunction "CT_3") (pintype "bidirectional"))
    )
    (net (code "81") (name "Net-(U6-SENSE)") (class "Default")
      (node (ref "C40") (pin "1") (pinfunction "1_1") (pintype "passive"))
      (node (ref "R49") (pin "2") (pinfunction "2_2") (pintype "passive"))
      (node (ref "R50") (pin "1") (pinfunction "1_1") (pintype "passive"))
      (node (ref "U6") (pin "2") (pinfunction "SENSE_2") (pintype "bidirectional"))
    )
    (net (code "82") (name "PCIE_RX_N") (class "Default")
      (node (ref "R18") (pin "2") (pinfunction "2_2") (pintype "passive"))
      (node (ref "R4") (pin "2") (pinfunction "2_2") (pintype "passive"))
      (node (ref "U5") (pin "8") (pinfunction "PCIE_RX_N_8") (pintype "bidirectional"))
    )
    (net (code "83") (name "PCIE_RX_P") (class "Default")
      (node (ref "R23") (pin "2") (pinfunction "2_2") (pintype "passive"))
      (node (ref "R30") (pin "2") (pinfunction "2_2") (pintype "passive"))
      (node (ref "U5") (pin "7") (pinfunction "PCIE_RX_P_7") (pintype "bidirectional"))
    )
    (net (code "84") (name "PCIE_TX_N") (class "Default")
      (node (ref "R24") (pin "2") (pinfunction "2_2") (pintype "passive"))
      (node (ref "U5") (pin "4") (pinfunction "PCIE_TX_N_4") (pintype "bidirectional"))
    )
    (net (code "85") (name "PCIE_TX_P") (class "Default")
      (node (ref "R25") (pin "2") (pinfunction "2_2") (pintype "passive"))
      (node (ref "U5") (pin "5") (pinfunction "PCIE_TX_P_5") (pintype "bidirectional"))
    )
    (net (code "86") (name "PCIE_~{RST}") (class "Default")
      (node (ref "J2") (pin "9") (pinfunction "9_9") (pintype "passive"))
    )
    (net (code "87") (name "PGOOD4$2") (class "Default")
      (node (ref "U5") (pin "37") (pinfunction "PGOOD4_37") (pintype "bidirectional"))
      (node (ref "U6") (pin "4") (pinfunction "~{MR}_4") (pintype "bidirectional"))
    )
    (net (code "88") (name "PG_3.3$3") (class "Default")
      (node (ref "IC1") (pin "13") (pinfunction "PG_13") (pintype "output"))
      (node (ref "R1") (pin "1") (pinfunction "1_1") (pintype "passive"))
    )
    (net (code "89") (name "PI_LED_~{PWR}") (class "Default")
      (node (ref "J3") (pin "95") (pinfunction "95_95") (pintype "passive"))
    )
    (net (code "90") (name "PI_~{LED_ACT}") (class "Default")
      (node (ref "J3") (pin "21") (pinfunction "21_21") (pintype "passive"))
    )
    (net (code "91") (name "PMIC_EN$2") (class "Default")
      (node (ref "R21") (pin "1") (pinfunction "1_1") (pintype "passive"))
      (node (ref "R46") (pin "1") (pinfunction "1_1") (pintype "passive"))
      (node (ref "U5") (pin "53") (pinfunction "PMIC_EN_53") (pintype "bidirectional"))
    )
    (net (code "92") (name "RUN_PG") (class "Default")
      (node (ref "Q6") (pin "1") (pinfunction "G_1") (pintype "passive"))
      (node (ref "R40") (pin "2") (pinfunction "2_2") (pintype "passive"))
      (node (ref "R44") (pin "1") (pinfunction "1_1") (pintype "passive"))
    )
    (net (code "93") (name "RUN_PG$") (class "Default")
      (node (ref "J3") (pin "92") (pinfunction "92_92") (pintype "passive"))
      (node (ref "R40") (pin "1") (pinfunction "1_1") (pintype "passive"))
    )
    (net (code "94") (name "SD_ALRM$2") (class "Default")
      (node (ref "U5") (pin "82") (pinfunction "SD_ALRM_82") (pintype "bidirectional"))
    )
    (net (code "95") (name "SD_PWR_ON") (class "Default")
      (node (ref "J3") (pin "75") (pinfunction "75_75") (pintype "passive"))
    )
    (net (code "96") (name "SD_VDD_OV") (class "Default")
      (node (ref "J3") (pin "73") (pinfunction "73_73") (pintype "passive"))
    )
    (net (code "97") (name "SW_3.3$3") (class "Default")
      (node (ref "IC1") (pin "14") (pinfunction "SW_14") (pintype "input"))
      (node (ref "IC1") (pin "15") (pinfunction "SW_15") (pintype "input"))
      (node (ref "L1") (pin "1") (pinfunction "1_1") (pintype "passive"))
    )
    (net (code "98") (name "TRDXCT0$5") (class "Default")
      (node (ref "J1") (pin "12") (pinfunction "TRDXCT0_12") (pintype "bidirectional"))
      (node (ref "R19") (pin "1") (pinfunction "1_1") (pintype "passive"))
    )
    (net (code "99") (name "TRDXCT1$5") (class "Default")
      (node (ref "J1") (pin "6") (pinfunction "TRDXCT1_6") (pintype "bidirectional"))
      (node (ref "R22") (pin "1") (pinfunction "1_1") (pintype "passive"))
    )
    (net (code "100") (name "TRDXCT2$5") (class "Default")
      (node (ref "J1") (pin "1") (pinfunction "TRDXCT2_1") (pintype "bidirectional"))
      (node (ref "R28") (pin "1") (pinfunction "1_1") (pintype "passive"))
    )
    (net (code "101") (name "TRDXCT3$5") (class "Default")
      (node (ref "J1") (pin "7") (pinfunction "TRDXCT3_7") (pintype "bidirectional"))
      (node (ref "R29") (pin "1") (pinfunction "1_1") (pintype "passive"))
    )
    (net (code "102") (name "USB_SEL$2") (class "Default")
      (node (ref "R39") (pin "2") (pinfunction "2_2") (pintype "passive"))
      (node (ref "R60") (pin "1") (pinfunction "1_1") (pintype "passive"))
      (node (ref "U5") (pin "83") (pinfunction "USB_SEL_83") (pintype "bidirectional"))
    )
    (net (code "103") (name "V1.8$2") (class "Default")
      (node (ref "Q2") (pin "1") (pinfunction "G_1") (pintype "passive"))
      (node (ref "R21") (pin "2") (pinfunction "2_2") (pintype "passive"))
      (node (ref "R41") (pin "2") (pinfunction "2_2") (pintype "passive"))
      (node (ref "R45") (pin "2") (pinfunction "2_2") (pintype "passive"))
      (node (ref "R48") (pin "2") (pinfunction "2_2") (pintype "passive"))
      (node (ref "R58") (pin "1") (pinfunction "1_1") (pintype "passive"))
      (node (ref "R60") (pin "2") (pinfunction "2_2") (pintype "passive"))
    )
    (net (code "104") (name "V1.8_OUT$2") (class "Default")
      (node (ref "C16") (pin "1") (pinfunction "1_1") (pintype "passive"))
      (node (ref "R41") (pin "1") (pinfunction "1_1") (pintype "passive"))
      (node (ref "U7") (pin "5") (pinfunction "VOUT_5") (pintype "power_in"))
    )
    (net (code "105") (name "VDAC_COMP") (class "Default")
      (node (ref "J2") (pin "11") (pinfunction "11_11") (pintype "passive"))
    )
    (net (code "106") (name "VLOGIC") (class "Default")
      (node (ref "C38") (pin "1") (pinfunction "1_1") (pintype "passive"))
      (node (ref "R37") (pin "1") (pinfunction "1_1") (pintype "passive"))
      (node (ref "R50") (pin "2") (pinfunction "2_2") (pintype "passive"))
      (node (ref "U6") (pin "1") (pinfunction "VDD_1") (pintype "bidirectional"))
    )
    (net (code "107") (name "unconnected-(J2-Pad4)") (class "Default")
      (node (ref "J2") (pin "4") (pinfunction "4_4") (pintype "passive"))
    )
    (net (code "108") (name "unconnected-(J2-Pad6)") (class "Default")
      (node (ref "J2") (pin "6") (pinfunction "6_6") (pintype "passive"))
    )
    (net (code "109") (name "unconnected-(J2-Pad28)") (class "Default")
      (node (ref "J2") (pin "28") (pinfunction "28_28") (pintype "passive"))
    )
    (net (code "110") (name "unconnected-(J2-Pad30)") (class "Default")
      (node (ref "J2") (pin "30") (pinfunction "30_30") (pintype "passive"))
    )
    (net (code "111") (name "unconnected-(J2-Pad34)") (class "Default")
      (node (ref "J2") (pin "34") (pinfunction "34_34") (pintype "passive"))
    )
    (net (code "112") (name "unconnected-(J2-Pad36)") (class "Default")
      (node (ref "J2") (pin "36") (pinfunction "36_36") (pintype "passive"))
    )
    (net (code "113") (name "unconnected-(J2-Pad40)") (class "Default")
      (node (ref "J2") (pin "40") (pinfunction "40_40") (pintype "passive"))
    )
    (net (code "114") (name "unconnected-(J2-Pad42)") (class "Default")
      (node (ref "J2") (pin "42") (pinfunction "42_42") (pintype "passive"))
    )
    (net (code "115") (name "unconnected-(J2-Pad43)") (class "Default")
      (node (ref "J2") (pin "43") (pinfunction "43_43") (pintype "passive"))
    )
    (net (code "116") (name "unconnected-(J2-Pad45)") (class "Default")
      (node (ref "J2") (pin "45") (pinfunction "45_45") (pintype "passive"))
    )
    (net (code "117") (name "unconnected-(J2-Pad46)") (class "Default")
      (node (ref "J2") (pin "46") (pinfunction "46_46") (pintype "passive"))
    )
    (net (code "118") (name "unconnected-(J2-Pad47)") (class "Default")
      (node (ref "J2") (pin "47") (pinfunction "47_47") (pintype "passive"))
    )
    (net (code "119") (name "unconnected-(J2-Pad48)") (class "Default")
      (node (ref "J2") (pin "48") (pinfunction "48_48") (pintype "passive"))
    )
    (net (code "120") (name "unconnected-(J2-Pad49)") (class "Default")
      (node (ref "J2") (pin "49") (pinfunction "49_49") (pintype "passive"))
    )
    (net (code "121") (name "unconnected-(J2-Pad51)") (class "Default")
      (node (ref "J2") (pin "51") (pinfunction "51_51") (pintype "passive"))
    )
    (net (code "122") (name "unconnected-(J2-Pad52)") (class "Default")
      (node (ref "J2") (pin "52") (pinfunction "52_52") (pintype "passive"))
    )
    (net (code "123") (name "unconnected-(J2-Pad53)") (class "Default")
      (node (ref "J2") (pin "53") (pinfunction "53_53") (pintype "passive"))
    )
    (net (code "124") (name "unconnected-(J2-Pad54)") (class "Default")
      (node (ref "J2") (pin "54") (pinfunction "54_54") (pintype "passive"))
    )
    (net (code "125") (name "unconnected-(J2-Pad57)") (class "Default")
      (node (ref "J2") (pin "57") (pinfunction "57_57") (pintype "passive"))
    )
    (net (code "126") (name "unconnected-(J2-Pad58)") (class "Default")
      (node (ref "J2") (pin "58") (pinfunction "58_58") (pintype "passive"))
    )
    (net (code "127") (name "unconnected-(J2-Pad59)") (class "Default")
      (node (ref "J2") (pin "59") (pinfunction "59_59") (pintype "passive"))
    )
    (net (code "128") (name "unconnected-(J2-Pad60)") (class "Default")
      (node (ref "J2") (pin "60") (pinfunction "60_60") (pintype "passive"))
    )
    (net (code "129") (name "unconnected-(J2-Pad63)") (class "Default")
      (node (ref "J2") (pin "63") (pinfunction "63_63") (pintype "passive"))
    )
    (net (code "130") (name "unconnected-(J2-Pad64)") (class "Default")
      (node (ref "J2") (pin "64") (pinfunction "64_64") (pintype "passive"))
    )
    (net (code "131") (name "unconnected-(J2-Pad65)") (class "Default")
      (node (ref "J2") (pin "65") (pinfunction "65_65") (pintype "passive"))
    )
    (net (code "132") (name "unconnected-(J2-Pad66)") (class "Default")
      (node (ref "J2") (pin "66") (pinfunction "66_66") (pintype "passive"))
    )
    (net (code "133") (name "unconnected-(J2-Pad69)") (class "Default")
      (node (ref "J2") (pin "69") (pinfunction "69_69") (pintype "passive"))
    )
    (net (code "134") (name "unconnected-(J2-Pad70)") (class "Default")
      (node (ref "J2") (pin "70") (pinfunction "70_70") (pintype "passive"))
    )
    (net (code "135") (name "unconnected-(J2-Pad71)") (class "Default")
      (node (ref "J2") (pin "71") (pinfunction "71_71") (pintype "passive"))
    )
    (net (code "136") (name "unconnected-(J2-Pad72)") (class "Default")
      (node (ref "J2") (pin "72") (pinfunction "72_72") (pintype "passive"))
    )
    (net (code "137") (name "unconnected-(J2-Pad75)") (class "Default")
      (node (ref "J2") (pin "75") (pinfunction "75_75") (pintype "passive"))
    )
    (net (code "138") (name "unconnected-(J2-Pad76)") (class "Default")
      (node (ref "J2") (pin "76") (pinfunction "76_76") (pintype "passive"))
    )
    (net (code "139") (name "unconnected-(J2-Pad77)") (class "Default")
      (node (ref "J2") (pin "77") (pinfunction "77_77") (pintype "passive"))
    )
    (net (code "140") (name "unconnected-(J2-Pad78)") (class "Default")
      (node (ref "J2") (pin "78") (pinfunction "78_78") (pintype "passive"))
    )
    (net (code "141") (name "unconnected-(J2-Pad81)") (class "Default")
      (node (ref "J2") (pin "81") (pinfunction "81_81") (pintype "passive"))
    )
    (net (code "142") (name "unconnected-(J2-Pad82)") (class "Default")
      (node (ref "J2") (pin "82") (pinfunction "82_82") (pintype "passive"))
    )
    (net (code "143") (name "unconnected-(J2-Pad83)") (class "Default")
      (node (ref "J2") (pin "83") (pinfunction "83_83") (pintype "passive"))
    )
    (net (code "144") (name "unconnected-(J2-Pad84)") (class "Default")
      (node (ref "J2") (pin "84") (pinfunction "84_84") (pintype "passive"))
    )
    (net (code "145") (name "unconnected-(J2-Pad87)") (class "Default")
      (node (ref "J2") (pin "87") (pinfunction "87_87") (pintype "passive"))
    )
    (net (code "146") (name "unconnected-(J2-Pad88)") (class "Default")
      (node (ref "J2") (pin "88") (pinfunction "88_88") (pintype "passive"))
    )
    (net (code "147") (name "unconnected-(J2-Pad89)") (class "Default")
      (node (ref "J2") (pin "89") (pinfunction "89_89") (pintype "passive"))
    )
    (net (code "148") (name "unconnected-(J2-Pad90)") (class "Default")
      (node (ref "J2") (pin "90") (pinfunction "90_90") (pintype "passive"))
    )
    (net (code "149") (name "unconnected-(J2-Pad93)") (class "Default")
      (node (ref "J2") (pin "93") (pinfunction "93_93") (pintype "passive"))
    )
    (net (code "150") (name "unconnected-(J2-Pad94)") (class "Default")
      (node (ref "J2") (pin "94") (pinfunction "94_94") (pintype "passive"))
    )
    (net (code "151") (name "unconnected-(J2-Pad95)") (class "Default")
      (node (ref "J2") (pin "95") (pinfunction "95_95") (pintype "passive"))
    )
    (net (code "152") (name "unconnected-(J2-Pad96)") (class "Default")
      (node (ref "J2") (pin "96") (pinfunction "96_96") (pintype "passive"))
    )
    (net (code "153") (name "unconnected-(J2-Pad99)") (class "Default")
      (node (ref "J2") (pin "99") (pinfunction "99_99") (pintype "passive"))
    )
    (net (code "154") (name "unconnected-(J2-Pad100)") (class "Default")
      (node (ref "J2") (pin "100") (pinfunction "100_100") (pintype "passive"))
    )
    (net (code "155") (name "unconnected-(J3-Pad24)") (class "Default")
      (node (ref "J3") (pin "24") (pinfunction "24_24") (pintype "passive"))
    )
    (net (code "156") (name "unconnected-(J3-Pad28)") (class "Default")
      (node (ref "J3") (pin "28") (pinfunction "28_28") (pintype "passive"))
    )
    (net (code "157") (name "unconnected-(J3-Pad29)") (class "Default")
      (node (ref "J3") (pin "29") (pinfunction "29_29") (pintype "passive"))
    )
    (net (code "158") (name "unconnected-(J3-Pad30)") (class "Default")
      (node (ref "J3") (pin "30") (pinfunction "30_30") (pintype "passive"))
    )
    (net (code "159") (name "unconnected-(J3-Pad31)") (class "Default")
      (node (ref "J3") (pin "31") (pinfunction "31_31") (pintype "passive"))
    )
    (net (code "160") (name "unconnected-(J3-Pad34)") (class "Default")
      (node (ref "J3") (pin "34") (pinfunction "34_34") (pintype "passive"))
    )
    (net (code "161") (name "unconnected-(J3-Pad37)") (class "Default")
      (node (ref "J3") (pin "37") (pinfunction "37_37") (pintype "passive"))
    )
    (net (code "162") (name "unconnected-(J3-Pad38)") (class "Default")
      (node (ref "J3") (pin "38") (pinfunction "38_38") (pintype "passive"))
    )
    (net (code "163") (name "unconnected-(J3-Pad39)") (class "Default")
      (node (ref "J3") (pin "39") (pinfunction "39_39") (pintype "passive"))
    )
    (net (code "164") (name "unconnected-(J3-Pad40)") (class "Default")
      (node (ref "J3") (pin "40") (pinfunction "40_40") (pintype "passive"))
    )
    (net (code "165") (name "unconnected-(J3-Pad41)") (class "Default")
      (node (ref "J3") (pin "41") (pinfunction "41_41") (pintype "passive"))
    )
    (net (code "166") (name "unconnected-(J3-Pad44)") (class "Default")
      (node (ref "J3") (pin "44") (pinfunction "44_44") (pintype "passive"))
    )
    (net (code "167") (name "unconnected-(J3-Pad45)") (class "Default")
      (node (ref "J3") (pin "45") (pinfunction "45_45") (pintype "passive"))
    )
    (net (code "168") (name "unconnected-(J3-Pad46)") (class "Default")
      (node (ref "J3") (pin "46") (pinfunction "46_46") (pintype "passive"))
    )
    (net (code "169") (name "unconnected-(J3-Pad47)") (class "Default")
      (node (ref "J3") (pin "47") (pinfunction "47_47") (pintype "passive"))
    )
    (net (code "170") (name "unconnected-(J3-Pad48)") (class "Default")
      (node (ref "J3") (pin "48") (pinfunction "48_48") (pintype "passive"))
    )
    (net (code "171") (name "unconnected-(J3-Pad50)") (class "Default")
      (node (ref "J3") (pin "50") (pinfunction "50_50") (pintype "passive"))
    )
    (net (code "172") (name "unconnected-(J3-Pad51)") (class "Default")
      (node (ref "J3") (pin "51") (pinfunction "51_51") (pintype "passive"))
    )
    (net (code "173") (name "unconnected-(J3-Pad54)") (class "Default")
      (node (ref "J3") (pin "54") (pinfunction "54_54") (pintype "passive"))
    )
    (net (code "174") (name "unconnected-(J3-Pad55)") (class "Default")
      (node (ref "J3") (pin "55") (pinfunction "55_55") (pintype "passive"))
    )
    (net (code "175") (name "unconnected-(J3-Pad56)") (class "Default")
      (node (ref "J3") (pin "56") (pinfunction "56_56") (pintype "passive"))
    )
    (net (code "176") (name "unconnected-(J3-Pad57)") (class "Default")
      (node (ref "J3") (pin "57") (pinfunction "57_57") (pintype "passive"))
    )
    (net (code "177") (name "unconnected-(J3-Pad58)") (class "Default")
      (node (ref "J3") (pin "58") (pinfunction "58_58") (pintype "passive"))
    )
    (net (code "178") (name "unconnected-(J3-Pad61)") (class "Default")
      (node (ref "J3") (pin "61") (pinfunction "61_61") (pintype "passive"))
    )
    (net (code "179") (name "unconnected-(J3-Pad62)") (class "Default")
      (node (ref "J3") (pin "62") (pinfunction "62_62") (pintype "passive"))
    )
    (net (code "180") (name "unconnected-(J3-Pad63)") (class "Default")
      (node (ref "J3") (pin "63") (pinfunction "63_63") (pintype "passive"))
    )
    (net (code "181") (name "unconnected-(J3-Pad64)") (class "Default")
      (node (ref "J3") (pin "64") (pinfunction "64_64") (pintype "passive"))
    )
    (net (code "182") (name "unconnected-(J3-Pad67)") (class "Default")
      (node (ref "J3") (pin "67") (pinfunction "67_67") (pintype "passive"))
    )
    (net (code "183") (name "unconnected-(J3-Pad68)") (class "Default")
      (node (ref "J3") (pin "68") (pinfunction "68_68") (pintype "passive"))
    )
    (net (code "184") (name "unconnected-(J3-Pad69)") (class "Default")
      (node (ref "J3") (pin "69") (pinfunction "69_69") (pintype "passive"))
    )
    (net (code "185") (name "unconnected-(J3-Pad70)") (class "Default")
      (node (ref "J3") (pin "70") (pinfunction "70_70") (pintype "passive"))
    )
    (net (code "186") (name "unconnected-(J3-Pad72)") (class "Default")
      (node (ref "J3") (pin "72") (pinfunction "72_72") (pintype "passive"))
    )
    (net (code "187") (name "unconnected-(J3-Pad76)") (class "Default")
      (node (ref "J3") (pin "76") (pinfunction "76_76") (pintype "passive"))
    )
    (net (code "188") (name "unconnected-(J3-Pad80)") (class "Default")
      (node (ref "J3") (pin "80") (pinfunction "80_80") (pintype "passive"))
    )
    (net (code "189") (name "unconnected-(J3-Pad82)") (class "Default")
      (node (ref "J3") (pin "82") (pinfunction "82_82") (pintype "passive"))
    )
    (net (code "190") (name "unconnected-(J3-Pad89)") (class "Default")
      (node (ref "J3") (pin "89") (pinfunction "89_89") (pintype "passive"))
    )
    (net (code "191") (name "unconnected-(J3-Pad91)") (class "Default")
      (node (ref "J3") (pin "91") (pinfunction "91_91") (pintype "passive"))
    )
    (net (code "192") (name "unconnected-(J3-Pad94)") (class "Default")
      (node (ref "J3") (pin "94") (pinfunction "94_94") (pintype "passive"))
    )
    (net (code "193") (name "unconnected-(J3-Pad96)") (class "Default")
      (node (ref "J3") (pin "96") (pinfunction "96_96") (pintype "passive"))
    )
    (net (code "194") (name "unconnected-(J4-12-Pad1_12)") (class "Default")
      (node (ref "J4") (pin "1_12") (pinfunction "12_1_12") (pintype "passive"))
    )
    (net (code "195") (name "unconnected-(J4-13-Pad1_13)") (class "Default")
      (node (ref "J4") (pin "1_13") (pinfunction "13_1_13") (pintype "passive"))
    )
    (net (code "196") (name "unconnected-(J4-14-Pad1_14)") (class "Default")
      (node (ref "J4") (pin "1_14") (pinfunction "14_1_14") (pintype "passive"))
    )
    (net (code "197") (name "unconnected-(U2-ADJ-Pad9)") (class "Default")
      (node (ref "U2") (pin "9") (pinfunction "ADJ_9") (pintype "bidirectional"))
    )
    (net (code "198") (name "unconnected-(U2-CP1-Pad5)") (class "Default")
      (node (ref "U2") (pin "5") (pinfunction "CP1_5") (pintype "bidirectional"))
    )
    (net (code "199") (name "unconnected-(U2-CP2-Pad6)") (class "Default")
      (node (ref "U2") (pin "6") (pinfunction "CP2_6") (pintype "bidirectional"))
    )
    (net (code "200") (name "unconnected-(U5-PMIC_INT-Pad52)") (class "Default")
      (node (ref "U5") (pin "52") (pinfunction "PMIC_INT_52") (pintype "bidirectional"))
    )
    (net (code "201") (name "unconnected-(U5-RESERVED-Pad49)") (class "Default")
      (node (ref "U5") (pin "49") (pinfunction "RESERVED_49") (pintype "bidirectional"))
    )
    (net (code "202") (name "unconnected-(U5-RESERVED-Pad50)") (class "Default")
      (node (ref "U5") (pin "50") (pinfunction "RESERVED_50") (pintype "bidirectional"))
    )
    (net (code "203") (name "unconnected-(U5-RESERVED-Pad84)") (class "Default")
      (node (ref "U5") (pin "84") (pinfunction "RESERVED_84") (pintype "bidirectional"))
    )
    (net (code "204") (name "unconnected-(U5-RESERVED-Pad85)") (class "Default")
      (node (ref "U5") (pin "85") (pinfunction "RESERVED_85") (pintype "bidirectional"))
    )
    (net (code "205") (name "~{EXTRST$1}") (class "Default")
      (node (ref "J3") (pin "100") (pinfunction "100_100") (pintype "passive"))
      (node (ref "Q1") (pin "1") (pinfunction "G_1") (pintype "passive"))
      (node (ref "R55") (pin "2") (pinfunction "2_2") (pintype "passive"))
    )
    (net (code "206") (name "~{PCIE_CLKREQ$2}") (class "Default")
      (node (ref "Q2") (pin "2") (pinfunction "S_2") (pintype "passive"))
      (node (ref "R20") (pin "2") (pinfunction "2_2") (pintype "passive"))
      (node (ref "R47") (pin "1") (pinfunction "1_1") (pintype "passive"))
      (node (ref "R58") (pin "2") (pinfunction "2_2") (pintype "passive"))
      (node (ref "U5") (pin "78") (pinfunction "~{CLKREQ}_78") (pintype "bidirectional"))
    )
    (net (code "207") (name "~{RPIBOOT$1}") (class "Default")
      (node (ref "J3") (pin "93") (pinfunction "93_93") (pintype "passive"))
      (node (ref "S1") (pin "3") (pinfunction "B_3") (pintype "passive"))
      (node (ref "S1") (pin "4") (pinfunction "B'_4") (pintype "passive"))
    )
    (net (code "208") (name "~{RST$2}") (class "Default")
      (node (ref "R33") (pin "1") (pinfunction "1_1") (pintype "passive"))
      (node (ref "R34") (pin "1") (pinfunction "1_1") (pintype "passive"))
      (node (ref "U5") (pin "76") (pinfunction "~{RST}_76") (pintype "bidirectional"))
    )
    (net (code "209") (name "~{RST_DELAY$2}") (class "Default")
      (node (ref "R33") (pin "2") (pinfunction "2_2") (pintype "passive"))
      (node (ref "R48") (pin "1") (pinfunction "1_1") (pintype "passive"))
      (node (ref "U6") (pin "6") (pinfunction "~{RESET}_6") (pintype "bidirectional"))
    )
  )
)
